# POE_REGULADORES.net
KiCad netlist of a schematic drawn in EAGLE
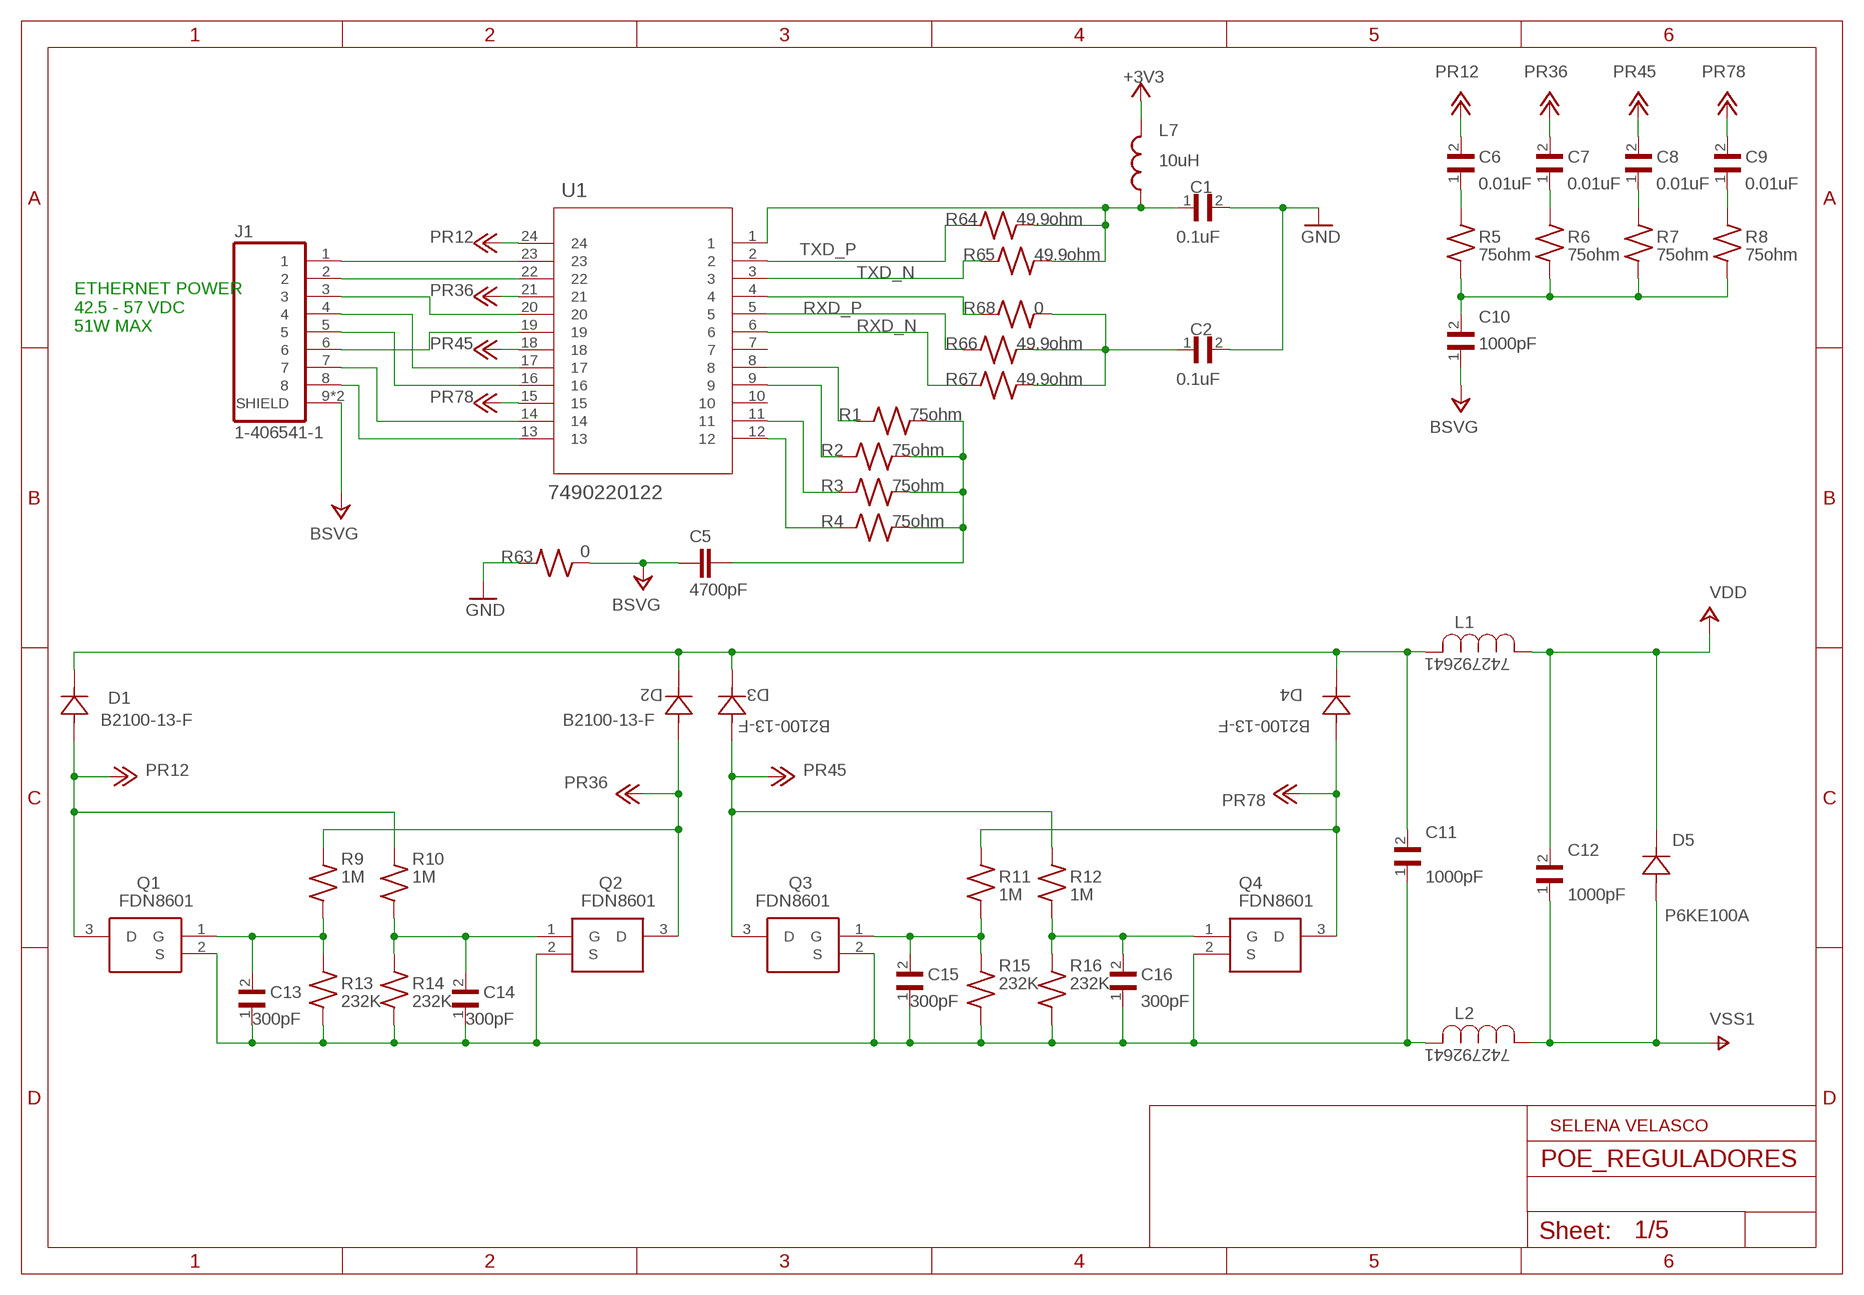
[diagram p0: schematic, sheet 1]
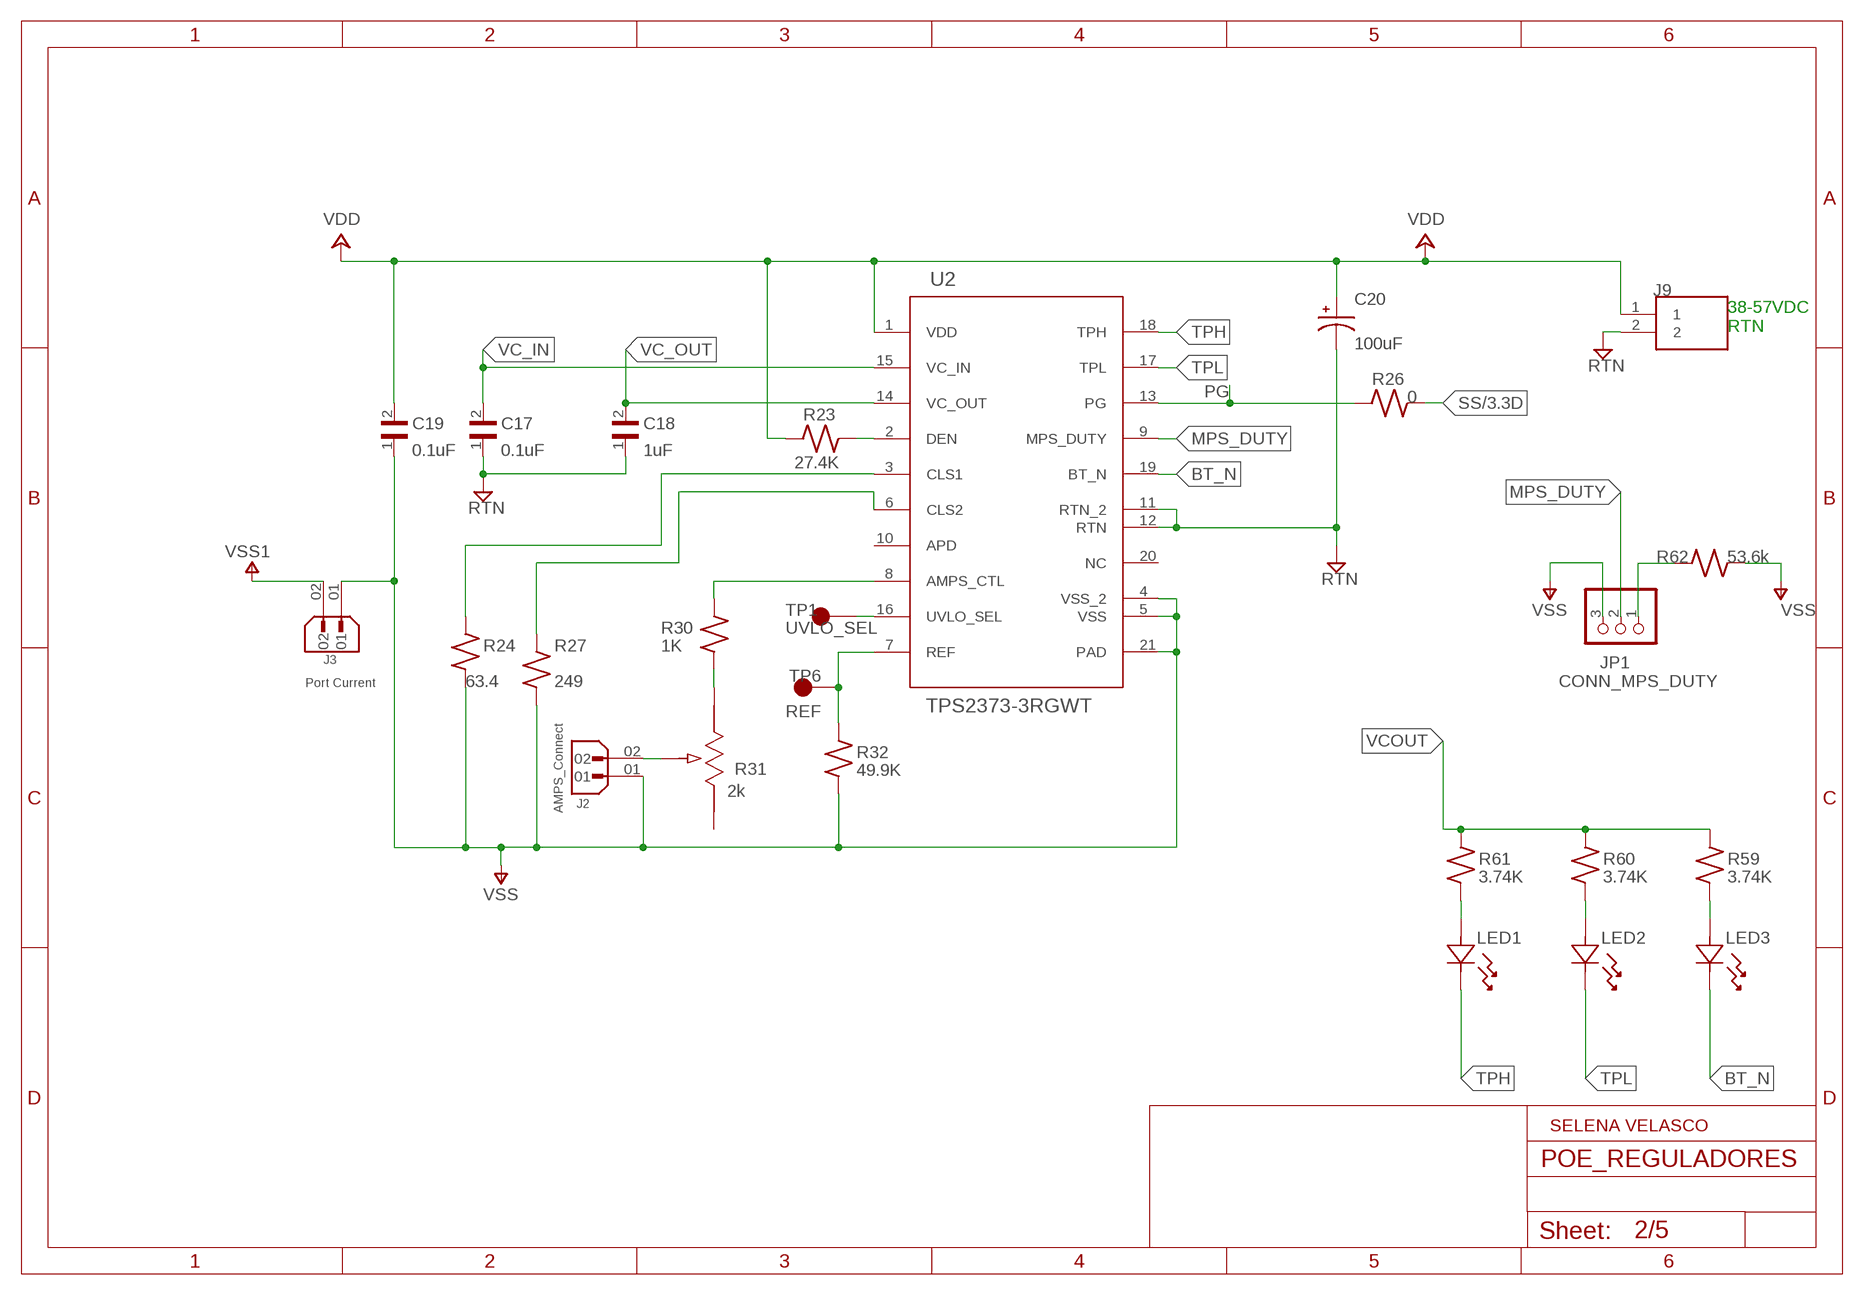
[diagram p1: schematic, sheet 2]
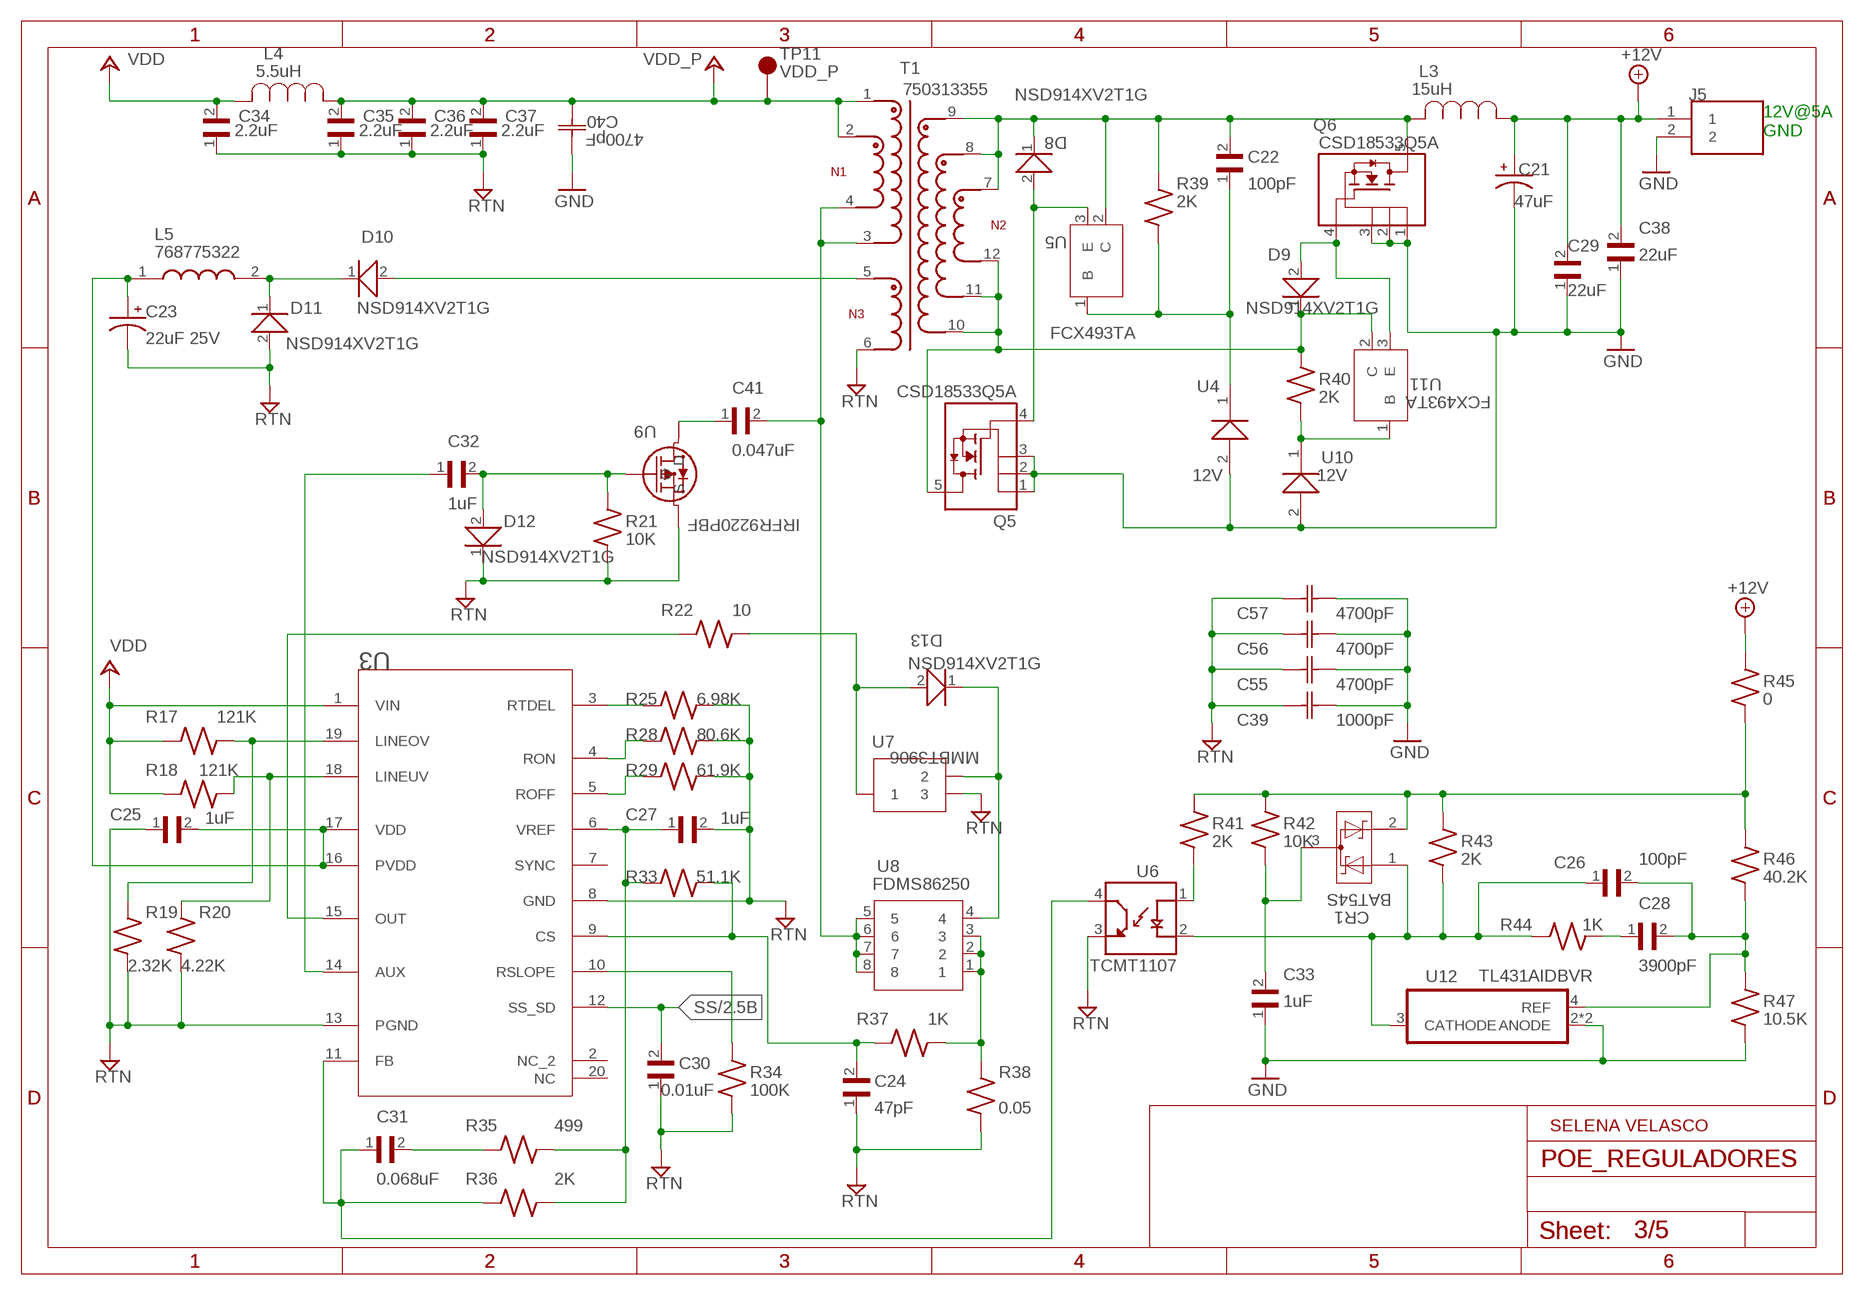
[diagram p2: schematic, sheet 3]
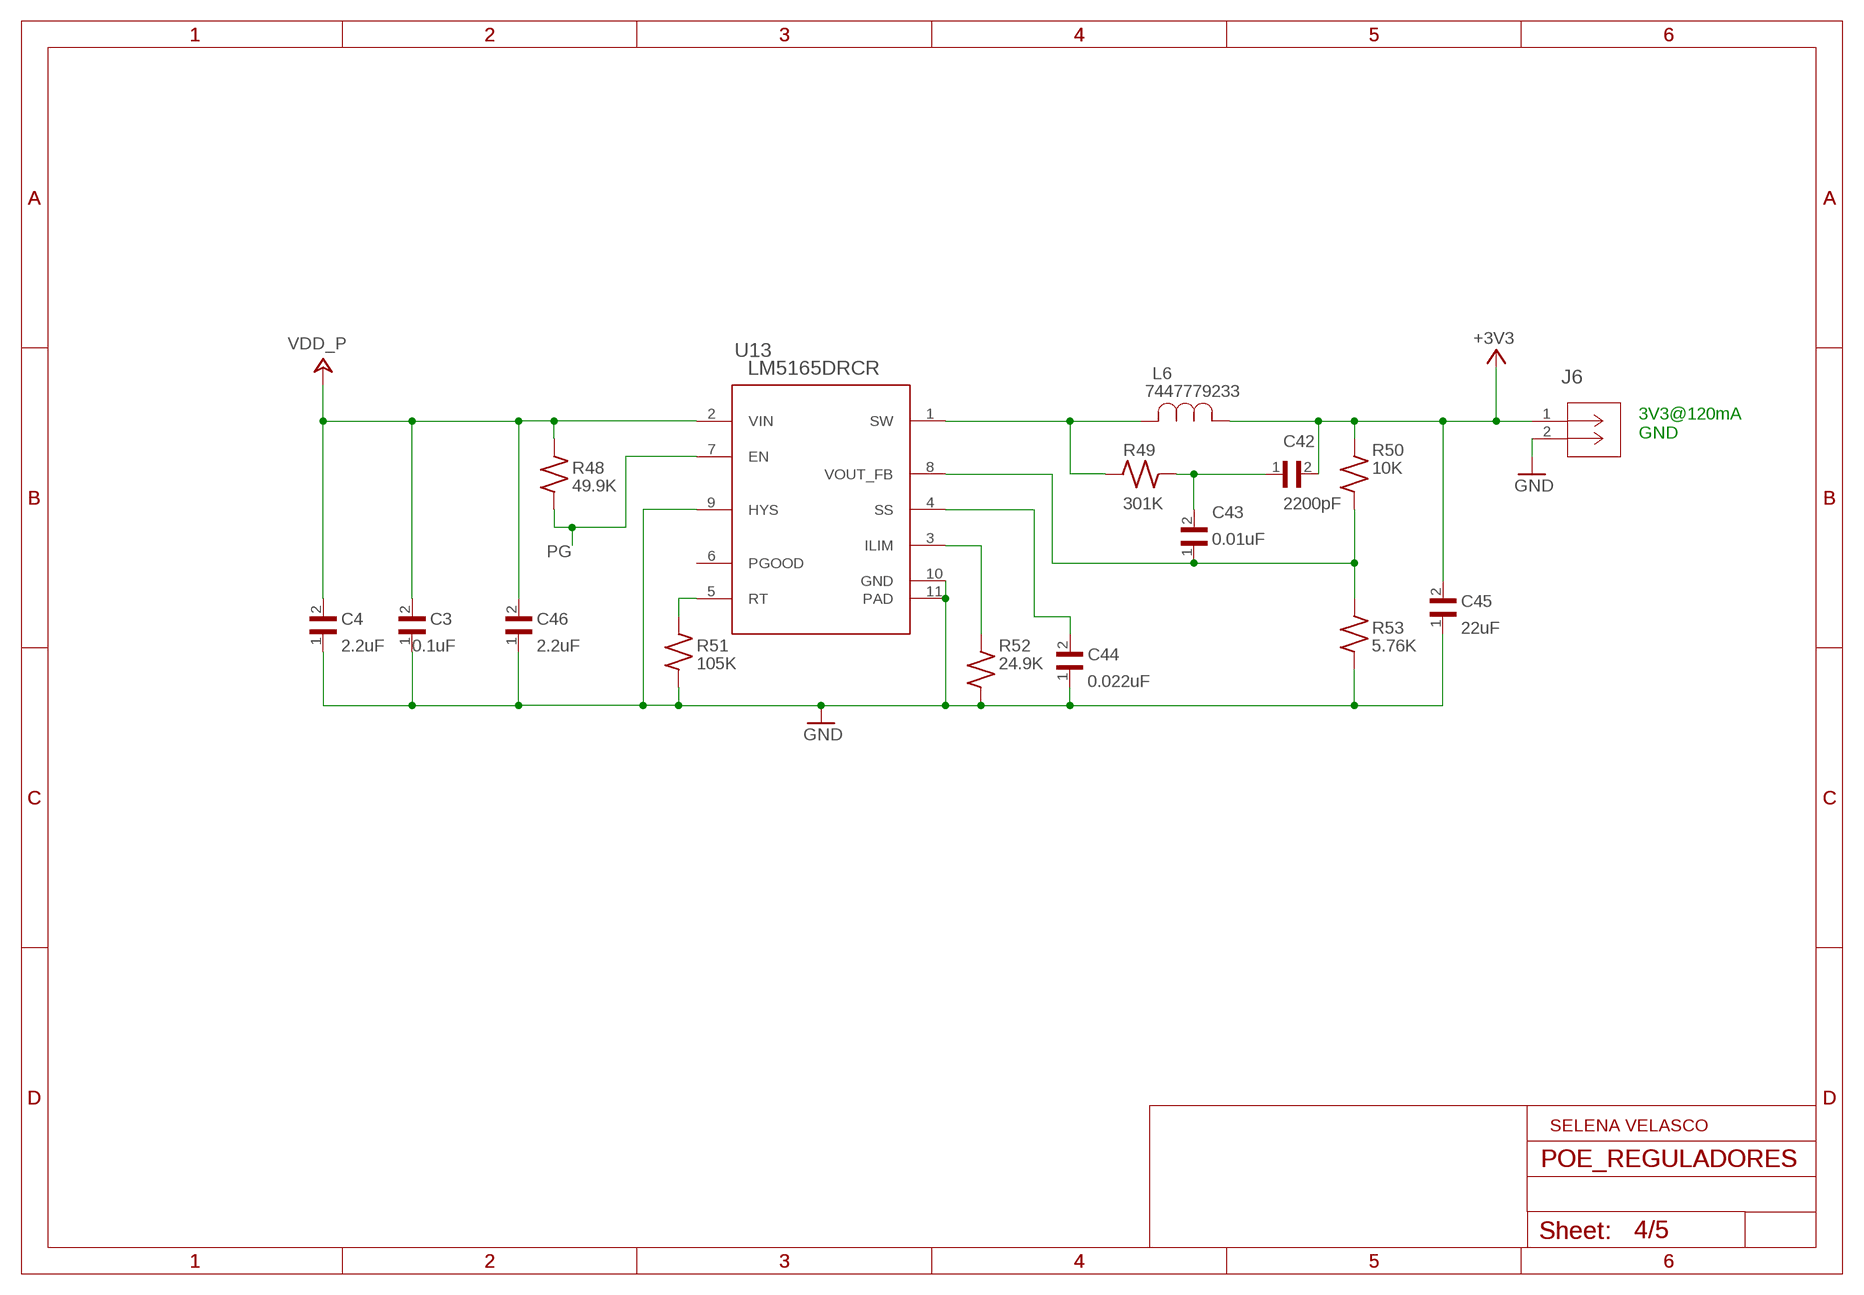
[diagram p3: schematic, sheet 4]
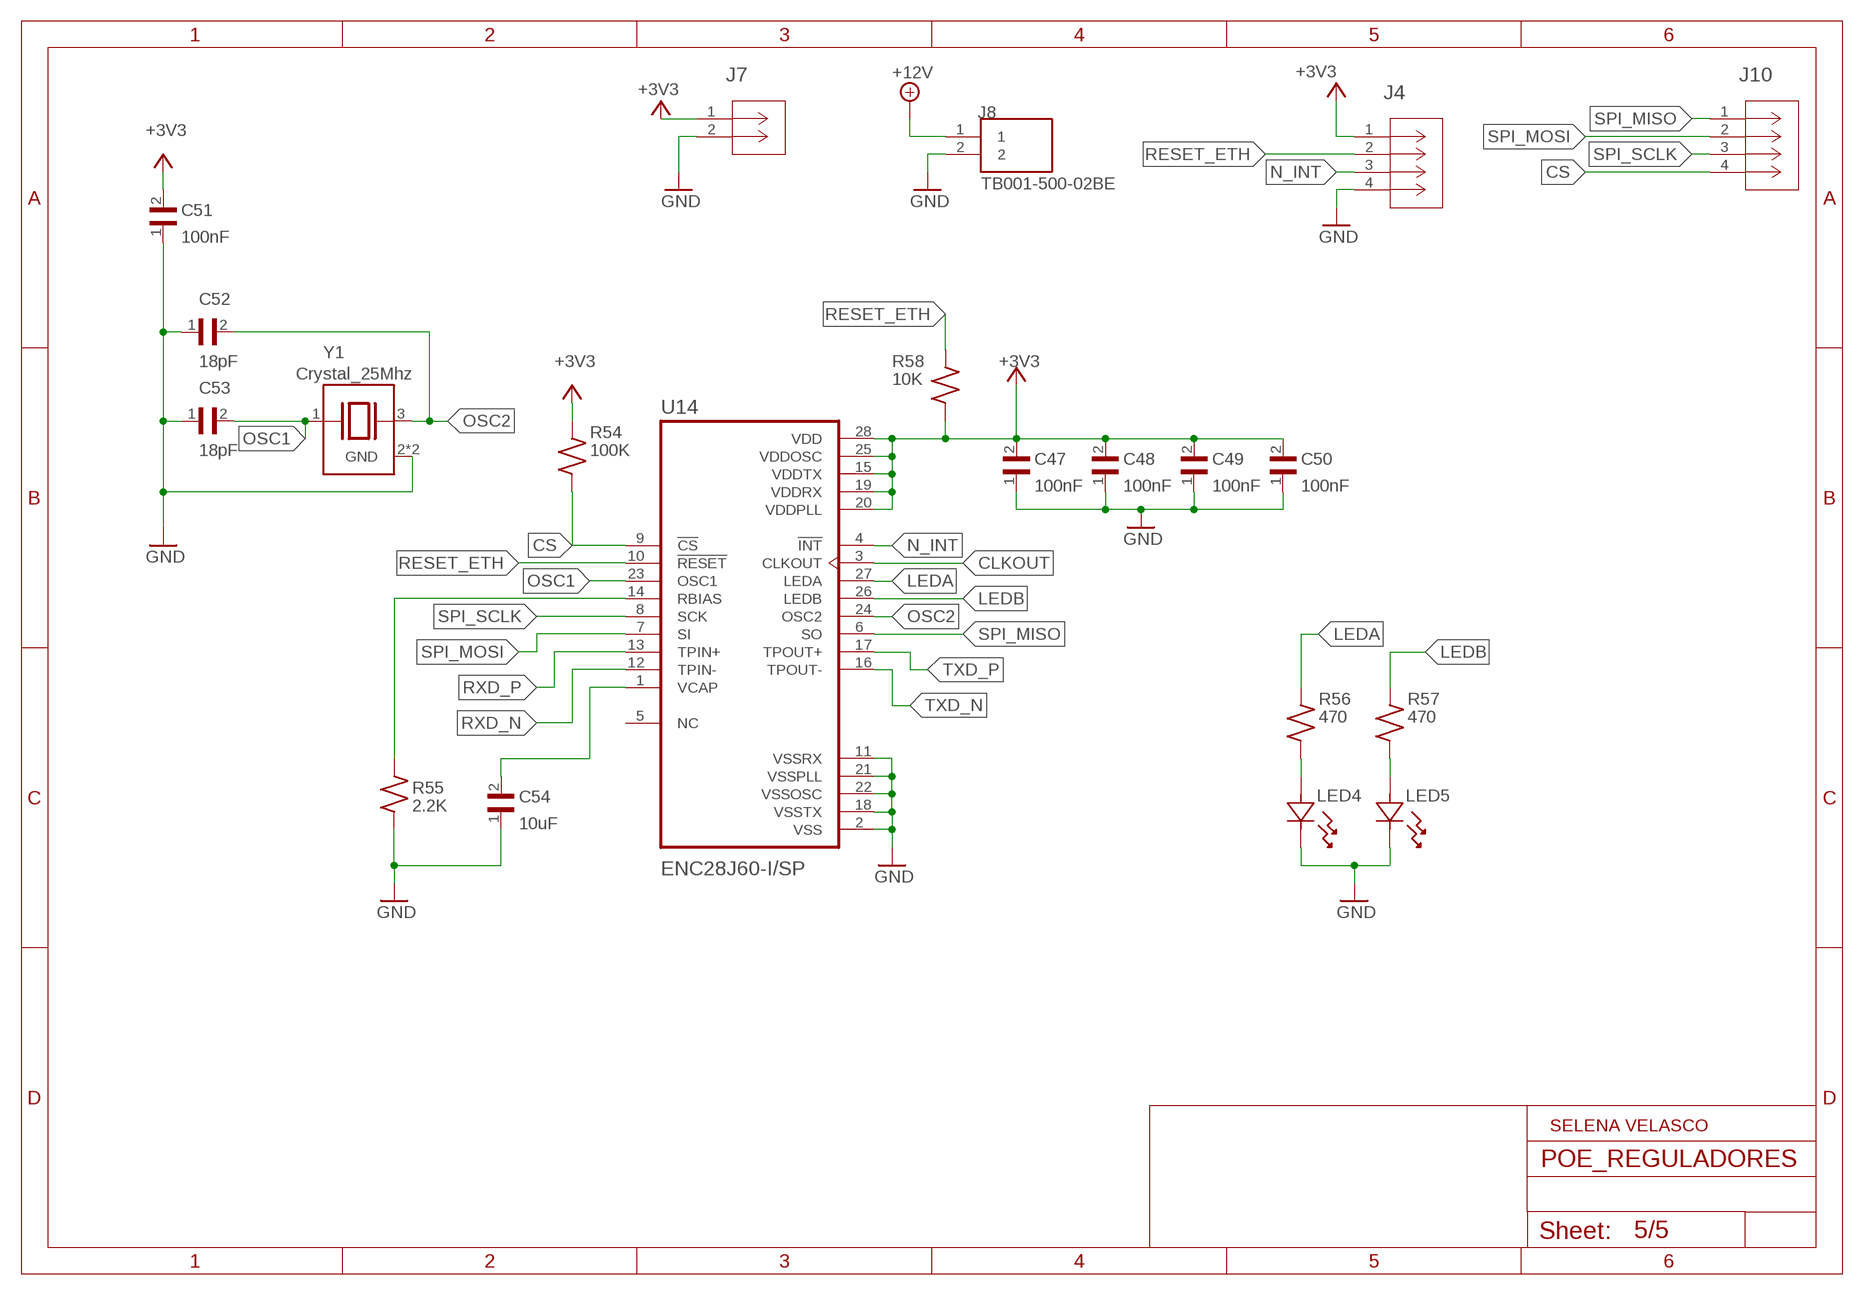
[diagram p4: schematic, sheet 5]

(export (version "E")
  (design (tool "Eeschema 10.0.6"))
  (components
    (comp (ref "C21")
      (value "47uF")
      (footprint "eagle-import:CAP_EEEFK1C470P")
      (fields (field (name "MANUFACTURER") "Panasonic"))
      (libsource (lib "eagle-import") (part "EEEFK1C470P"))
    )
    (comp (ref "C22")
      (value "100pF")
      (footprint "eagle-import:CAPC3316X98N")
      (libsource (lib "eagle-import") (part "C1206Y104K9RAC7800"))
    )
    (comp (ref "C23")
      (value "22uF 25V")
      (footprint "eagle-import:CAP_EEEFK1E220R")
      (fields (field (name "MANUFACTURER") "Panasonic"))
      (libsource (lib "eagle-import") (part "EEEFK1E220R"))
    )
    (comp (ref "C24")
      (value "47pF")
      (footprint "eagle-import:CAPC3316X98N")
      (libsource (lib "eagle-import") (part "C1206Y104K9RAC7800"))
    )
    (comp (ref "C25")
      (value "1uF")
      (footprint "eagle-import:CAPC3316X98N")
      (libsource (lib "eagle-import") (part "C1206Y104K9RAC7800"))
    )
    (comp (ref "C26")
      (value "100pF")
      (footprint "eagle-import:CAPC3316X98N")
      (libsource (lib "eagle-import") (part "C1206Y104K9RAC7800"))
    )
    (comp (ref "C27")
      (value "1uF")
      (footprint "eagle-import:CAPC3316X98N")
      (libsource (lib "eagle-import") (part "C1206Y104K9RAC7800"))
    )
    (comp (ref "C28")
      (value "3900pF")
      (footprint "eagle-import:CAPC3316X98N")
      (libsource (lib "eagle-import") (part "C1206Y104K9RAC7800"))
    )
    (comp (ref "C29")
      (value "22uF")
      (footprint "eagle-import:CAPC3316X98N")
      (libsource (lib "eagle-import") (part "C1206Y104K9RAC7800"))
    )
    (comp (ref "C30")
      (value "0.01uF")
      (footprint "eagle-import:CAPC3316X98N")
      (libsource (lib "eagle-import") (part "C1206Y104K9RAC7800"))
    )
    (comp (ref "C31")
      (value "0.068uF")
      (footprint "eagle-import:CAPC3316X98N")
      (libsource (lib "eagle-import") (part "C1206Y104K9RAC7800"))
    )
    (comp (ref "C32")
      (value "1uF")
      (footprint "eagle-import:CAPC3316X98N")
      (libsource (lib "eagle-import") (part "C1206Y104K9RAC7800"))
    )
    (comp (ref "C33")
      (value "1uF")
      (footprint "eagle-import:CAPC3316X98N")
      (libsource (lib "eagle-import") (part "C1206Y104K9RAC7800"))
    )
    (comp (ref "C34")
      (value "2.2uF")
      (footprint "eagle-import:CAPC3316X98N")
      (libsource (lib "eagle-import") (part "C1206Y104K9RAC7800"))
    )
    (comp (ref "C35")
      (value "2.2uF")
      (footprint "eagle-import:CAPC3316X98N")
      (libsource (lib "eagle-import") (part "C1206Y104K9RAC7800"))
    )
    (comp (ref "C36")
      (value "2.2uF")
      (footprint "eagle-import:CAPC3316X98N")
      (libsource (lib "eagle-import") (part "C1206Y104K9RAC7800"))
    )
    (comp (ref "C37")
      (value "2.2uF")
      (footprint "eagle-import:CAPC3316X98N")
      (libsource (lib "eagle-import") (part "C1206Y104K9RAC7800"))
    )
    (comp (ref "C38")
      (value "22uF")
      (footprint "eagle-import:CAPC3316X98N")
      (libsource (lib "eagle-import") (part "C1206Y104K9RAC7800"))
    )
    (comp (ref "C39")
      (value "1000pF")
      (footprint "eagle-import:CAP_1812_AVX")
      (fields
        (field (name "MANUFACTURER_PART_NUMBER") "1812GC472KAT1A")
        (field (name "COPYRIGHT") "Copyright (C) 2024 Ultra Librarian. All rights reserved.")
      )
      (libsource (lib "eagle-import") (part "1812GC472KAT1A"))
    )
    (comp (ref "C40")
      (value "4700pF")
      (footprint "eagle-import:CAP_1812_AVX")
      (fields
        (field (name "MANUFACTURER_PART_NUMBER") "1812GC472KAT1A")
        (field (name "COPYRIGHT") "Copyright (C) 2024 Ultra Librarian. All rights reserved.")
      )
      (libsource (lib "eagle-import") (part "1812GC472KAT1A"))
    )
    (comp (ref "C41")
      (value "0.047uF")
      (footprint "eagle-import:CAPC3316X98N")
      (libsource (lib "eagle-import") (part "C1206Y104K9RAC7800"))
    )
    (comp (ref "C55")
      (value "4700pF")
      (footprint "eagle-import:CAP_1812_AVX")
      (fields
        (field (name "MANUFACTURER_PART_NUMBER") "1812GC472KAT1A")
        (field (name "COPYRIGHT") "Copyright (C) 2024 Ultra Librarian. All rights reserved.")
      )
      (libsource (lib "eagle-import") (part "1812GC472KAT1A"))
    )
    (comp (ref "C56")
      (value "4700pF")
      (footprint "eagle-import:CAP_1812_AVX")
      (fields
        (field (name "MANUFACTURER_PART_NUMBER") "1812GC472KAT1A")
        (field (name "COPYRIGHT") "Copyright (C) 2024 Ultra Librarian. All rights reserved.")
      )
      (libsource (lib "eagle-import") (part "1812GC472KAT1A"))
    )
    (comp (ref "C57")
      (value "4700pF")
      (footprint "eagle-import:CAP_1812_AVX")
      (fields
        (field (name "MANUFACTURER_PART_NUMBER") "1812GC472KAT1A")
        (field (name "COPYRIGHT") "Copyright (C) 2024 Ultra Librarian. All rights reserved.")
      )
      (libsource (lib "eagle-import") (part "1812GC472KAT1A"))
    )
    (comp (ref "CR1")
      (value "BAT54S")
      (footprint "eagle-import:SOT-23_TO-236_DTC")
      (fields (field (name "COPYRIGHT") "Copyright (C) 2024 Ultra Librarian. All rights reserved."))
      (libsource (lib "eagle-import") (part "BAT54S"))
    )
    (comp (ref "D8")
      (value "NSD914XV2T1G")
      (footprint "eagle-import:SOD-523_0P9X1P3_ONS")
      (fields (field (name "COPYRIGHT") "Copyright (C) 2024 Ultra Librarian. All rights reserved."))
      (libsource (lib "eagle-import") (part "NSD914XV2T1G"))
    )
    (comp (ref "D9")
      (value "NSD914XV2T1G")
      (footprint "eagle-import:SOD-523_0P9X1P3_ONS")
      (fields (field (name "COPYRIGHT") "Copyright (C) 2024 Ultra Librarian. All rights reserved."))
      (libsource (lib "eagle-import") (part "NSD914XV2T1G"))
    )
    (comp (ref "D10")
      (value "NSD914XV2T1G")
      (footprint "eagle-import:SOD-523_0P9X1P3_ONS")
      (fields (field (name "COPYRIGHT") "Copyright (C) 2024 Ultra Librarian. All rights reserved."))
      (libsource (lib "eagle-import") (part "NSD914XV2T1G"))
    )
    (comp (ref "D11")
      (value "NSD914XV2T1G")
      (footprint "eagle-import:SOD-523_0P9X1P3_ONS")
      (fields (field (name "COPYRIGHT") "Copyright (C) 2024 Ultra Librarian. All rights reserved."))
      (libsource (lib "eagle-import") (part "NSD914XV2T1G"))
    )
    (comp (ref "D12")
      (value "NSD914XV2T1G")
      (footprint "eagle-import:SOD-523_0P9X1P3_ONS")
      (fields (field (name "COPYRIGHT") "Copyright (C) 2024 Ultra Librarian. All rights reserved."))
      (libsource (lib "eagle-import") (part "NSD914XV2T1G"))
    )
    (comp (ref "D13")
      (value "NSD914XV2T1G")
      (footprint "eagle-import:SOD-523_0P9X1P3_ONS")
      (fields (field (name "COPYRIGHT") "Copyright (C) 2024 Ultra Librarian. All rights reserved."))
      (libsource (lib "eagle-import") (part "NSD914XV2T1G"))
    )
    (comp (ref "J5")
      (value "TB001-500-02BE")
      (footprint "eagle-import:CUI_TB001-500-02BE")
      (fields (field (name "MANUFACTURER") "CUI"))
      (libsource (lib "eagle-import") (part "TB001-500-02BE"))
    )
    (comp (ref "L3")
      (value "15uH")
      (footprint "eagle-import:IND_1890_2-WE-HCI_WRE")
      (fields
        (field (name "MANUFACTURER_PART_NUMBER") "74435571500")
        (field (name "COPYRIGHT") "Copyright (C) 2024 Ultra Librarian. All rights reserved.")
      )
      (libsource (lib "eagle-import") (part "74435571500"))
    )
    (comp (ref "L4")
      (value "5.5uH")
      (footprint "eagle-import:IND_1050-WE-HCI_WRE")
      (fields
        (field (name "MANUFACTURER_PART_NUMBER") "744325550")
        (field (name "COPYRIGHT") "Copyright (C) 2024 Ultra Librarian. All rights reserved.")
      )
      (libsource (lib "eagle-import") (part "744325550"))
    )
    (comp (ref "L5")
      (value "768775322")
      (footprint "eagle-import:768775322")
      (fields (field (name "MOUSER_PART_NUMBER") "710-768775322"))
      (libsource (lib "eagle-import") (part "768775322"))
    )
    (comp (ref "Q5")
      (value "CSD18533Q5A")
      (footprint "eagle-import:TRANS_CSD18533Q5A")
      (fields (field (name "MANUFACTURER") "Texas Instruments"))
      (libsource (lib "eagle-import") (part "CSD18533Q5A"))
    )
    (comp (ref "Q6")
      (value "CSD18533Q5A")
      (footprint "eagle-import:TRANS_CSD18533Q5A")
      (fields (field (name "MANUFACTURER") "Texas Instruments"))
      (libsource (lib "eagle-import") (part "CSD18533Q5A"))
    )
    (comp (ref "R17")
      (value "121K")
      (footprint "eagle-import:RESC3116X65N")
      (libsource (lib "eagle-import") (part "RC1206FR-071ML"))
    )
    (comp (ref "R18")
      (value "121K")
      (footprint "eagle-import:RESC3116X65N")
      (libsource (lib "eagle-import") (part "RC1206FR-071ML"))
    )
    (comp (ref "R19")
      (value "2.32K")
      (footprint "eagle-import:RESC3116X65N")
      (libsource (lib "eagle-import") (part "RC1206FR-071ML"))
    )
    (comp (ref "R20")
      (value "4.22K")
      (footprint "eagle-import:RESC3116X65N")
      (libsource (lib "eagle-import") (part "RC1206FR-071ML"))
    )
    (comp (ref "R21")
      (value "10K")
      (footprint "eagle-import:RESC3116X65N")
      (libsource (lib "eagle-import") (part "RC1206FR-071ML"))
    )
    (comp (ref "R22")
      (value "10")
      (footprint "eagle-import:RESC3116X65N")
      (libsource (lib "eagle-import") (part "RC1206FR-071ML"))
    )
    (comp (ref "R25")
      (value "6.98K")
      (footprint "eagle-import:RESC3116X65N")
      (libsource (lib "eagle-import") (part "RC1206FR-071ML"))
    )
    (comp (ref "R28")
      (value "80.6K")
      (footprint "eagle-import:RESC3116X65N")
      (libsource (lib "eagle-import") (part "RC1206FR-071ML"))
    )
    (comp (ref "R29")
      (value "61.9K")
      (footprint "eagle-import:RESC3116X65N")
      (libsource (lib "eagle-import") (part "RC1206FR-071ML"))
    )
    (comp (ref "R33")
      (value "51.1K")
      (footprint "eagle-import:RESC3116X65N")
      (libsource (lib "eagle-import") (part "RC1206FR-071ML"))
    )
    (comp (ref "R34")
      (value "100K")
      (footprint "eagle-import:RESC3116X65N")
      (libsource (lib "eagle-import") (part "RC1206FR-071ML"))
    )
    (comp (ref "R35")
      (value "499")
      (footprint "eagle-import:RESC3116X65N")
      (libsource (lib "eagle-import") (part "RC1206FR-071ML"))
    )
    (comp (ref "R36")
      (value "2K")
      (footprint "eagle-import:RESC3116X65N")
      (libsource (lib "eagle-import") (part "RC1206FR-071ML"))
    )
    (comp (ref "R37")
      (value "1K")
      (footprint "eagle-import:RESC3116X65N")
      (libsource (lib "eagle-import") (part "RC1206FR-071ML"))
    )
    (comp (ref "R38")
      (value "0.05")
      (footprint "eagle-import:RESC3116X65N")
      (libsource (lib "eagle-import") (part "RC1206FR-071ML"))
    )
    (comp (ref "R39")
      (value "2K")
      (footprint "eagle-import:RESC3116X65N")
      (libsource (lib "eagle-import") (part "RC1206FR-071ML"))
    )
    (comp (ref "R40")
      (value "2K")
      (footprint "eagle-import:RESC3116X65N")
      (libsource (lib "eagle-import") (part "RC1206FR-071ML"))
    )
    (comp (ref "R41")
      (value "2K")
      (footprint "eagle-import:RESC3116X65N")
      (libsource (lib "eagle-import") (part "RC1206FR-071ML"))
    )
    (comp (ref "R42")
      (value "10K")
      (footprint "eagle-import:RESC3116X65N")
      (libsource (lib "eagle-import") (part "RC1206FR-071ML"))
    )
    (comp (ref "R43")
      (value "2K")
      (footprint "eagle-import:RESC3116X65N")
      (libsource (lib "eagle-import") (part "RC1206FR-071ML"))
    )
    (comp (ref "R44")
      (value "1K")
      (footprint "eagle-import:RESC3116X65N")
      (libsource (lib "eagle-import") (part "RC1206FR-071ML"))
    )
    (comp (ref "R45")
      (value "0")
      (footprint "eagle-import:RESC3116X65N")
      (libsource (lib "eagle-import") (part "RC1206FR-071ML"))
    )
    (comp (ref "R46")
      (value "40.2K")
      (footprint "eagle-import:RESC3116X65N")
      (libsource (lib "eagle-import") (part "RC1206FR-071ML"))
    )
    (comp (ref "R47")
      (value "10.5K")
      (footprint "eagle-import:RESC3116X65N")
      (libsource (lib "eagle-import") (part "RC1206FR-071ML"))
    )
    (comp (ref "T1")
      (value "750313355")
      (footprint "eagle-import:WE-POE++_EFD20_L29.65W21.8H11.43")
      (libsource (lib "eagle-import") (part "750313355"))
    )
    (comp (ref "TP11")
      (value "VDD_P")
      (footprint "eagle-import:KEYSTONE_5019")
      (fields (field (name "MANUFACTURER") "Keystone Electronics"))
      (libsource (lib "eagle-import") (part "5019"))
    )
    (comp (ref "U3")
      (value "UCC2897APW")
      (footprint "eagle-import:PW0020A")
      (fields (field (name "COPYRIGHT") "Copyright (C) 2024 Ultra Librarian. All rights reserved."))
      (libsource (lib "eagle-import") (part "UCC2897APW"))
    )
    (comp (ref "U4")
      (value "12V")
      (footprint "eagle-import:SOD-123_ONS")
      (fields
        (field (name "MANUFACTURER_PART_NUMBER") "MMSZ5242BT3G")
        (field (name "COPYRIGHT") "Copyright (C) 2024 Ultra Librarian. All rights reserved.")
      )
      (libsource (lib "eagle-import") (part "MMSZ5242BT3G"))
    )
    (comp (ref "U5")
      (value "FCX493TA")
      (footprint "eagle-import:FCX493TA_DIO")
      (fields (field (name "COPYRIGHT") "Copyright (C) 2024 Ultra Librarian. All rights reserved."))
      (libsource (lib "eagle-import") (part "FCX493TA"))
    )
    (comp (ref "U6")
      (value "TCMT1107")
      (footprint "eagle-import:SOIC127P700X230-4N")
      (fields (field (name "MANUFACTURER") "Vishay"))
      (libsource (lib "eagle-import") (part "TCMT1107"))
    )
    (comp (ref "U7")
      (value "MMBT3906")
      (footprint "eagle-import:SOT-23-3_1P4X3P040_ONS")
      (fields
        (field (name "MANUFACTURER_PART_NUMBER") "SMMBT3906LT1G")
        (field (name "COPYRIGHT") "Copyright (C) 2024 Ultra Librarian. All rights reserved.")
      )
      (libsource (lib "eagle-import") (part "SMMBT3906LT1G"))
    )
    (comp (ref "U8")
      (value "FDMS86250")
      (footprint "eagle-import:FDMS_86250_ONS")
      (fields (field (name "COPYRIGHT") "Copyright (C) 2024 Ultra Librarian. All rights reserved."))
      (libsource (lib "eagle-import") (part "FDMS86250"))
    )
    (comp (ref "U9")
      (value "IRFR9220PBF")
      (footprint "eagle-import:DPAK_VIS")
      (fields (field (name "COPYRIGHT") "Copyright (C) 2024 Ultra Librarian. All rights reserved."))
      (libsource (lib "eagle-import") (part "IRFR9220PBF"))
    )
    (comp (ref "U10")
      (value "12V")
      (footprint "eagle-import:SOD-123_ONS")
      (fields
        (field (name "MANUFACTURER_PART_NUMBER") "MMSZ5242BT3G")
        (field (name "COPYRIGHT") "Copyright (C) 2024 Ultra Librarian. All rights reserved.")
      )
      (libsource (lib "eagle-import") (part "MMSZ5242BT3G"))
    )
    (comp (ref "U11")
      (value "FCX493TA")
      (footprint "eagle-import:FCX493TA_DIO")
      (fields (field (name "COPYRIGHT") "Copyright (C) 2024 Ultra Librarian. All rights reserved."))
      (libsource (lib "eagle-import") (part "FCX493TA"))
    )
    (comp (ref "U12")
      (value "TL431AIDBVR")
      (footprint "eagle-import:SOT95P280X145-5N")
      (libsource (lib "eagle-import") (part "TL431AIDBVR"))
    )
    (comp (ref "C17")
      (value "0.1uF")
      (footprint "eagle-import:CAPC3316X98N")
      (libsource (lib "eagle-import") (part "C1206Y104K9RAC7800"))
    )
    (comp (ref "C18")
      (value "1uF")
      (footprint "eagle-import:CAPC3316X98N")
      (libsource (lib "eagle-import") (part "C1206Y104K9RAC7800"))
    )
    (comp (ref "C19")
      (value "0.1uF")
      (footprint "eagle-import:CAPC3316X98N")
      (libsource (lib "eagle-import") (part "C1206Y104K9RAC7800"))
    )
    (comp (ref "C20")
      (value "100uF")
      (footprint "eagle-import:CAP_EEEFK1J470P")
      (fields (field (name "MANUFACTURER") "Panasonic"))
      (libsource (lib "eagle-import") (part "EEEFK1J470P"))
    )
    (comp (ref "J2")
      (value "AMPS_Connect")
      (footprint "eagle-import:WURTH_61300211121")
      (fields (field (name "MF") "Würth Elektronik") (field (name "MP") "61300211121"))
      (libsource (lib "eagle-import") (part "61300211121"))
    )
    (comp (ref "J3")
      (value "Port Current")
      (footprint "eagle-import:WURTH_61300211121")
      (fields (field (name "MF") "Würth Elektronik") (field (name "MP") "61300211121"))
      (libsource (lib "eagle-import") (part "61300211121"))
    )
    (comp (ref "J9")
      (value "TB001-500-02BE")
      (footprint "eagle-import:CUI_TB001-500-02BE")
      (fields (field (name "MANUFACTURER") "CUI"))
      (libsource (lib "eagle-import") (part "TB001-500-02BE"))
    )
    (comp (ref "JP1")
      (value "CONN_MPS_DUTY")
      (footprint "eagle-import:1X03")
      (libsource (lib "eagle-import") (part "PINHD-1X3"))
    )
    (comp (ref "LED1")
      (value "BL-BGE1V1")
      (footprint "eagle-import:BL-BGE1V1_AMB")
      (fields (field (name "COPYRIGHT") "Copyright (C) 2024 Ultra Librarian. All rights reserved."))
      (libsource (lib "eagle-import") (part "BL-BGE1V1"))
    )
    (comp (ref "LED2")
      (value "BL-BGE1V1")
      (footprint "eagle-import:BL-BGE1V1_AMB")
      (fields (field (name "COPYRIGHT") "Copyright (C) 2024 Ultra Librarian. All rights reserved."))
      (libsource (lib "eagle-import") (part "BL-BGE1V1"))
    )
    (comp (ref "LED3")
      (value "BL-BGE1V1")
      (footprint "eagle-import:BL-BGE1V1_AMB")
      (fields (field (name "COPYRIGHT") "Copyright (C) 2024 Ultra Librarian. All rights reserved."))
      (libsource (lib "eagle-import") (part "BL-BGE1V1"))
    )
    (comp (ref "R23")
      (value "27.4K")
      (footprint "eagle-import:RESC3116X65N")
      (libsource (lib "eagle-import") (part "RC1206FR-071ML"))
    )
    (comp (ref "R24")
      (value "63.4")
      (footprint "eagle-import:RESC3116X65N")
      (libsource (lib "eagle-import") (part "RC1206FR-071ML"))
    )
    (comp (ref "R26")
      (value "0")
      (footprint "eagle-import:RESC3116X65N")
      (libsource (lib "eagle-import") (part "RC1206FR-071ML"))
    )
    (comp (ref "R27")
      (value "249")
      (footprint "eagle-import:RESC3116X65N")
      (libsource (lib "eagle-import") (part "RC1206FR-071ML"))
    )
    (comp (ref "R30")
      (value "1K")
      (footprint "eagle-import:RESC3116X65N")
      (libsource (lib "eagle-import") (part "RC1206FR-071ML"))
    )
    (comp (ref "R31")
      (value "2k")
      (footprint "eagle-import:POT_3386P")
      (fields
        (field (name "MANUFACTURER_PART_NUMBER") "3386P-1-202LF")
        (field (name "COPYRIGHT") "Copyright (C) 2024 Ultra Librarian. All rights reserved.")
      )
      (libsource (lib "eagle-import") (part "3386P-1-202LF"))
    )
    (comp (ref "R32")
      (value "49.9K")
      (footprint "eagle-import:RESC3116X65N")
      (libsource (lib "eagle-import") (part "RC1206FR-071ML"))
    )
    (comp (ref "R59")
      (value "3.74K")
      (footprint "eagle-import:RESC3116X65N")
      (libsource (lib "eagle-import") (part "RC1206FR-071ML"))
    )
    (comp (ref "R60")
      (value "3.74K")
      (footprint "eagle-import:RESC3116X65N")
      (libsource (lib "eagle-import") (part "RC1206FR-071ML"))
    )
    (comp (ref "R61")
      (value "3.74K")
      (footprint "eagle-import:RESC3116X65N")
      (libsource (lib "eagle-import") (part "RC1206FR-071ML"))
    )
    (comp (ref "R62")
      (value "53.6k")
      (footprint "eagle-import:RESC3116X65N")
      (libsource (lib "eagle-import") (part "RC1206FR-071ML"))
    )
    (comp (ref "TP1")
      (value "UVLO_SEL")
      (footprint "eagle-import:KEYSTONE_5019")
      (fields (field (name "MANUFACTURER") "Keystone Electronics"))
      (libsource (lib "eagle-import") (part "5019"))
    )
    (comp (ref "TP6")
      (value "REF")
      (footprint "eagle-import:KEYSTONE_5019")
      (fields (field (name "MANUFACTURER") "Keystone Electronics"))
      (libsource (lib "eagle-import") (part "5019"))
    )
    (comp (ref "U2")
      (value "TPS2373-3RGWT")
      (footprint "eagle-import:RGW0020B")
      (fields (field (name "COPYRIGHT") "Copyright (C) 2024 Ultra Librarian. All rights reserved."))
      (libsource (lib "eagle-import") (part "TPS2373-3RGWT"))
    )
    (comp (ref "C1")
      (value "0.1uF")
      (footprint "eagle-import:CAPC3316X98N")
      (libsource (lib "eagle-import") (part "C1206Y104K9RAC7800"))
    )
    (comp (ref "C2")
      (value "0.1uF")
      (footprint "eagle-import:CAPC3316X98N")
      (libsource (lib "eagle-import") (part "C1206Y104K9RAC7800"))
    )
    (comp (ref "C5")
      (value "4700pF")
      (footprint "eagle-import:C4532")
      (libsource (lib "eagle-import") (part "C-EUC4532"))
    )
    (comp (ref "C6")
      (value "0.01uF")
      (footprint "eagle-import:CAPC3316X98N")
      (libsource (lib "eagle-import") (part "C1206Y104K9RAC7800"))
    )
    (comp (ref "C7")
      (value "0.01uF")
      (footprint "eagle-import:CAPC3316X98N")
      (libsource (lib "eagle-import") (part "C1206Y104K9RAC7800"))
    )
    (comp (ref "C8")
      (value "0.01uF")
      (footprint "eagle-import:CAPC3316X98N")
      (libsource (lib "eagle-import") (part "C1206Y104K9RAC7800"))
    )
    (comp (ref "C9")
      (value "0.01uF")
      (footprint "eagle-import:CAPC3316X98N")
      (libsource (lib "eagle-import") (part "C1206Y104K9RAC7800"))
    )
    (comp (ref "C10")
      (value "1000pF")
      (footprint "eagle-import:CAPC4520X150N")
      (libsource (lib "eagle-import") (part "GR442QR73D102KW01L"))
    )
    (comp (ref "C11")
      (value "1000pF")
      (footprint "eagle-import:CAPC3316X98N")
      (libsource (lib "eagle-import") (part "C1206Y104K9RAC7800"))
    )
    (comp (ref "C12")
      (value "1000pF")
      (footprint "eagle-import:CAPC3316X98N")
      (libsource (lib "eagle-import") (part "C1206Y104K9RAC7800"))
    )
    (comp (ref "C13")
      (value "300pF")
      (footprint "eagle-import:CAPC3316X98N")
      (libsource (lib "eagle-import") (part "C1206Y104K9RAC7800"))
    )
    (comp (ref "C14")
      (value "300pF")
      (footprint "eagle-import:CAPC3316X98N")
      (libsource (lib "eagle-import") (part "C1206Y104K9RAC7800"))
    )
    (comp (ref "C15")
      (value "300pF")
      (footprint "eagle-import:CAPC3316X98N")
      (libsource (lib "eagle-import") (part "C1206Y104K9RAC7800"))
    )
    (comp (ref "C16")
      (value "300pF")
      (footprint "eagle-import:CAPC3316X98N")
      (libsource (lib "eagle-import") (part "C1206Y104K9RAC7800"))
    )
    (comp (ref "D1")
      (value "B2100-13-F")
      (footprint "eagle-import:SMB_DIO")
      (fields (field (name "COPYRIGHT") "Copyright (C) 2024 Ultra Librarian. All rights reserved."))
      (libsource (lib "eagle-import") (part "B2100-13-F"))
    )
    (comp (ref "D2")
      (value "B2100-13-F")
      (footprint "eagle-import:SMB_DIO")
      (fields (field (name "COPYRIGHT") "Copyright (C) 2024 Ultra Librarian. All rights reserved."))
      (libsource (lib "eagle-import") (part "B2100-13-F"))
    )
    (comp (ref "D3")
      (value "B2100-13-F")
      (footprint "eagle-import:SMB_DIO")
      (fields (field (name "COPYRIGHT") "Copyright (C) 2024 Ultra Librarian. All rights reserved."))
      (libsource (lib "eagle-import") (part "B2100-13-F"))
    )
    (comp (ref "D4")
      (value "B2100-13-F")
      (footprint "eagle-import:SMB_DIO")
      (fields (field (name "COPYRIGHT") "Copyright (C) 2024 Ultra Librarian. All rights reserved."))
      (libsource (lib "eagle-import") (part "B2100-13-F"))
    )
    (comp (ref "D5")
      (value "P6KE100A")
      (footprint "eagle-import:P6KESERIES_LTF")
      (fields (field (name "COPYRIGHT") "Copyright (C) 2024 Ultra Librarian. All rights reserved."))
      (libsource (lib "eagle-import") (part "P6KE100A"))
    )
    (comp (ref "J1")
      (value "1-406541-1")
      (footprint "eagle-import:CONN_1-406541-1")
      (fields (field (name "MANUFACTURER") "TE CONNECTIVITY") (field (name "PUBLISHER") "TE_CONNECTIVITY"))
      (libsource (lib "eagle-import") (part "1-406541-1"))
    )
    (comp (ref "L1")
      (value "742792641")
      (footprint "eagle-import:IND_742792641_WRE")
      (fields (field (name "COPYRIGHT") "Copyright (C) 2024 Ultra Librarian. All rights reserved."))
      (libsource (lib "eagle-import") (part "742792641"))
    )
    (comp (ref "L2")
      (value "742792641")
      (footprint "eagle-import:IND_742792641_WRE")
      (fields (field (name "COPYRIGHT") "Copyright (C) 2024 Ultra Librarian. All rights reserved."))
      (libsource (lib "eagle-import") (part "742792641"))
    )
    (comp (ref "L7")
      (value "10uH")
      (footprint "eagle-import:INDM3225X210N")
      (fields (field (name "MANUFACTURER") "TDK"))
      (libsource (lib "eagle-import") (part "B82422T1103K000"))
    )
    (comp (ref "Q1")
      (value "FDN8601")
      (footprint "eagle-import:SOT95P251X112-3N")
      (fields (field (name "MOUSER_PART_NUMBER") "512-FDN8601"))
      (libsource (lib "eagle-import") (part "FDN8601"))
    )
    (comp (ref "Q2")
      (value "FDN8601")
      (footprint "eagle-import:SOT95P251X112-3N")
      (fields (field (name "MOUSER_PART_NUMBER") "512-FDN8601"))
      (libsource (lib "eagle-import") (part "FDN8601"))
    )
    (comp (ref "Q3")
      (value "FDN8601")
      (footprint "eagle-import:SOT95P251X112-3N")
      (fields (field (name "MOUSER_PART_NUMBER") "512-FDN8601"))
      (libsource (lib "eagle-import") (part "FDN8601"))
    )
    (comp (ref "Q4")
      (value "FDN8601")
      (footprint "eagle-import:SOT95P251X112-3N")
      (fields (field (name "MOUSER_PART_NUMBER") "512-FDN8601"))
      (libsource (lib "eagle-import") (part "FDN8601"))
    )
    (comp (ref "R1")
      (value "75ohm")
      (footprint "eagle-import:RESC3116X65N")
      (libsource (lib "eagle-import") (part "RC1206FR-071ML"))
    )
    (comp (ref "R2")
      (value "75ohm")
      (footprint "eagle-import:RESC3116X65N")
      (libsource (lib "eagle-import") (part "RC1206FR-071ML"))
    )
    (comp (ref "R3")
      (value "75ohm")
      (footprint "eagle-import:RESC3116X65N")
      (libsource (lib "eagle-import") (part "RC1206FR-071ML"))
    )
    (comp (ref "R4")
      (value "75ohm")
      (footprint "eagle-import:RESC3116X65N")
      (libsource (lib "eagle-import") (part "RC1206FR-071ML"))
    )
    (comp (ref "R5")
      (value "75ohm")
      (footprint "eagle-import:RESC3116X65N")
      (libsource (lib "eagle-import") (part "RC1206FR-071ML"))
    )
    (comp (ref "R6")
      (value "75ohm")
      (footprint "eagle-import:RESC3116X65N")
      (libsource (lib "eagle-import") (part "RC1206FR-071ML"))
    )
    (comp (ref "R7")
      (value "75ohm")
      (footprint "eagle-import:RESC3116X65N")
      (libsource (lib "eagle-import") (part "RC1206FR-071ML"))
    )
    (comp (ref "R8")
      (value "75ohm")
      (footprint "eagle-import:RESC3116X65N")
      (libsource (lib "eagle-import") (part "RC1206FR-071ML"))
    )
    (comp (ref "R9")
      (value "1M")
      (footprint "eagle-import:RESC3116X65N")
      (libsource (lib "eagle-import") (part "RC1206FR-071ML"))
    )
    (comp (ref "R10")
      (value "1M")
      (footprint "eagle-import:RESC3116X65N")
      (libsource (lib "eagle-import") (part "RC1206FR-071ML"))
    )
    (comp (ref "R11")
      (value "1M")
      (footprint "eagle-import:RESC3116X65N")
      (libsource (lib "eagle-import") (part "RC1206FR-071ML"))
    )
    (comp (ref "R12")
      (value "1M")
      (footprint "eagle-import:RESC3116X65N")
      (libsource (lib "eagle-import") (part "RC1206FR-071ML"))
    )
    (comp (ref "R13")
      (value "232K")
      (footprint "eagle-import:RESC3116X65N")
      (libsource (lib "eagle-import") (part "RC1206FR-071ML"))
    )
    (comp (ref "R14")
      (value "232K")
      (footprint "eagle-import:RESC3116X65N")
      (libsource (lib "eagle-import") (part "RC1206FR-071ML"))
    )
    (comp (ref "R15")
      (value "232K")
      (footprint "eagle-import:RESC3116X65N")
      (libsource (lib "eagle-import") (part "RC1206FR-071ML"))
    )
    (comp (ref "R16")
      (value "232K")
      (footprint "eagle-import:RESC3116X65N")
      (libsource (lib "eagle-import") (part "RC1206FR-071ML"))
    )
    (comp (ref "R63")
      (value "0")
      (footprint "eagle-import:RESC3116X65N")
      (libsource (lib "eagle-import") (part "RC1206FR-071ML"))
    )
    (comp (ref "R64")
      (value "49.9ohm")
      (footprint "eagle-import:RESC3116X65N")
      (libsource (lib "eagle-import") (part "RC1206FR-071ML"))
    )
    (comp (ref "R65")
      (value "49.9ohm")
      (footprint "eagle-import:RESC3116X65N")
      (libsource (lib "eagle-import") (part "RC1206FR-071ML"))
    )
    (comp (ref "R66")
      (value "49.9ohm")
      (footprint "eagle-import:RESC3116X65N")
      (libsource (lib "eagle-import") (part "RC1206FR-071ML"))
    )
    (comp (ref "R67")
      (value "49.9ohm")
      (footprint "eagle-import:RESC3116X65N")
      (libsource (lib "eagle-import") (part "RC1206FR-071ML"))
    )
    (comp (ref "R68")
      (value "0")
      (footprint "eagle-import:RESC3116X65N")
      (libsource (lib "eagle-import") (part "RC1206FR-071ML"))
    )
    (comp (ref "U1")
      (value "7490220122")
      (footprint "eagle-import:7490220122_WRE")
      (fields (field (name "COPYRIGHT") "Copyright (C) 2024 Ultra Librarian. All rights reserved."))
      (libsource (lib "eagle-import") (part "7490220122"))
    )
    (comp (ref "C47")
      (value "100nF")
      (footprint "eagle-import:CAPC3316X98N")
      (libsource (lib "eagle-import") (part "C1206Y104K9RAC7800"))
    )
    (comp (ref "C48")
      (value "100nF")
      (footprint "eagle-import:CAPC3316X98N")
      (libsource (lib "eagle-import") (part "C1206Y104K9RAC7800"))
    )
    (comp (ref "C49")
      (value "100nF")
      (footprint "eagle-import:CAPC3316X98N")
      (libsource (lib "eagle-import") (part "C1206Y104K9RAC7800"))
    )
    (comp (ref "C50")
      (value "100nF")
      (footprint "eagle-import:CAPC3316X98N")
      (libsource (lib "eagle-import") (part "C1206Y104K9RAC7800"))
    )
    (comp (ref "C51")
      (value "100nF")
      (footprint "eagle-import:CAPC3316X98N")
      (libsource (lib "eagle-import") (part "C1206Y104K9RAC7800"))
    )
    (comp (ref "C52")
      (value "18pF")
      (footprint "eagle-import:CAPC3316X98N")
      (libsource (lib "eagle-import") (part "C1206Y104K9RAC7800"))
    )
    (comp (ref "C53")
      (value "18pF")
      (footprint "eagle-import:CAPC3316X98N")
      (libsource (lib "eagle-import") (part "C1206Y104K9RAC7800"))
    )
    (comp (ref "C54")
      (value "10uF")
      (footprint "eagle-import:CAPC3316X98N")
      (libsource (lib "eagle-import") (part "C1206Y104K9RAC7800"))
    )
    (comp (ref "J4")
      (value "OSTVN04A150")
      (footprint "eagle-import:CONN_OSTVN04A150_OST")
      (fields (field (name "COPYRIGHT") "Copyright (C) 2024 Ultra Librarian. All rights reserved."))
      (libsource (lib "eagle-import") (part "OSTVN04A150"))
    )
    (comp (ref "J7")
      (value "OSTVN02A150")
      (footprint "eagle-import:CONN_OSTVN02A150_OST")
      (fields (field (name "COPYRIGHT") "Copyright (C) 2024 Ultra Librarian. All rights reserved."))
      (libsource (lib "eagle-import") (part "OSTVN02A150"))
    )
    (comp (ref "J8")
      (value "TB001-500-02BE")
      (footprint "eagle-import:CUI_TB001-500-02BE")
      (fields (field (name "MANUFACTURER") "CUI"))
      (libsource (lib "eagle-import") (part "TB001-500-02BE"))
    )
    (comp (ref "J10")
      (value "OSTVN04A150")
      (footprint "eagle-import:CONN_OSTVN04A150_OST")
      (fields (field (name "COPYRIGHT") "Copyright (C) 2024 Ultra Librarian. All rights reserved."))
      (libsource (lib "eagle-import") (part "OSTVN04A150"))
    )
    (comp (ref "LED4")
      (value "BL-BGE1V1")
      (footprint "eagle-import:BL-BGE1V1_AMB")
      (fields (field (name "COPYRIGHT") "Copyright (C) 2024 Ultra Librarian. All rights reserved."))
      (libsource (lib "eagle-import") (part "BL-BGE1V1"))
    )
    (comp (ref "LED5")
      (value "BL-BGE1V1")
      (footprint "eagle-import:BL-BGE1V1_AMB")
      (fields (field (name "COPYRIGHT") "Copyright (C) 2024 Ultra Librarian. All rights reserved."))
      (libsource (lib "eagle-import") (part "BL-BGE1V1"))
    )
    (comp (ref "R54")
      (value "100K")
      (footprint "eagle-import:RESC3116X65N")
      (libsource (lib "eagle-import") (part "RC1206FR-071ML"))
    )
    (comp (ref "R55")
      (value "2.2K")
      (footprint "eagle-import:RESC3116X65N")
      (libsource (lib "eagle-import") (part "RC1206FR-071ML"))
    )
    (comp (ref "R56")
      (value "470")
      (footprint "eagle-import:RESC3116X65N")
      (libsource (lib "eagle-import") (part "RC1206FR-071ML"))
    )
    (comp (ref "R57")
      (value "470")
      (footprint "eagle-import:RESC3116X65N")
      (libsource (lib "eagle-import") (part "RC1206FR-071ML"))
    )
    (comp (ref "R58")
      (value "10K")
      (footprint "eagle-import:RESC3116X65N")
      (libsource (lib "eagle-import") (part "RC1206FR-071ML"))
    )
    (comp (ref "U14")
      (value "ENC28J60-I/SP")
      (footprint "eagle-import:DIP787W45P254L3556H508Q28")
      (libsource (lib "eagle-import") (part "ENC28J60-I/SP"))
    )
    (comp (ref "Y1")
      (value "Crystal_25Mhz")
      (footprint "eagle-import:XTAL_TSX-3225_25.0000MF10P-C3")
      (fields (field (name "MANUFACTURER") "EPSON"))
      (libsource (lib "eagle-import") (part "TSX-3225_25.0000MF10P-C3"))
    )
    (comp (ref "C3")
      (value "0.1uF")
      (footprint "eagle-import:CAPC3316X98N")
      (libsource (lib "eagle-import") (part "C1206Y104K9RAC7800"))
    )
    (comp (ref "C4")
      (value "2.2uF")
      (footprint "eagle-import:CAPC3316X98N")
      (libsource (lib "eagle-import") (part "C1206Y104K9RAC7800"))
    )
    (comp (ref "C42")
      (value "2200pF")
      (footprint "eagle-import:CAPC3316X98N")
      (libsource (lib "eagle-import") (part "C1206Y104K9RAC7800"))
    )
    (comp (ref "C43")
      (value "0.01uF")
      (footprint "eagle-import:CAPC3316X98N")
      (libsource (lib "eagle-import") (part "C1206Y104K9RAC7800"))
    )
    (comp (ref "C44")
      (value "0.022uF")
      (footprint "eagle-import:CAPC3316X98N")
      (libsource (lib "eagle-import") (part "C1206Y104K9RAC7800"))
    )
    (comp (ref "C45")
      (value "22uF")
      (footprint "eagle-import:CAPC3316X98N")
      (libsource (lib "eagle-import") (part "C1206Y104K9RAC7800"))
    )
    (comp (ref "C46")
      (value "2.2uF")
      (footprint "eagle-import:CAPC3316X98N")
      (libsource (lib "eagle-import") (part "C1206Y104K9RAC7800"))
    )
    (comp (ref "J6")
      (value "OSTVN02A150")
      (footprint "eagle-import:CONN_OSTVN02A150_OST")
      (fields (field (name "COPYRIGHT") "Copyright (C) 2024 Ultra Librarian. All rights reserved."))
      (libsource (lib "eagle-import") (part "OSTVN02A150"))
    )
    (comp (ref "L6")
      (value "7447779233")
      (footprint "eagle-import:IND_7345R_WE-PD_WRE")
      (fields (field (name "COPYRIGHT") "Copyright (C) 2024 Ultra Librarian. All rights reserved."))
      (libsource (lib "eagle-import") (part "7447779233"))
    )
    (comp (ref "R48")
      (value "49.9K")
      (footprint "eagle-import:RESC3116X65N")
      (libsource (lib "eagle-import") (part "RC1206FR-071ML"))
    )
    (comp (ref "R49")
      (value "301K")
      (footprint "eagle-import:RESC3116X65N")
      (libsource (lib "eagle-import") (part "RC1206FR-071ML"))
    )
    (comp (ref "R50")
      (value "10K")
      (footprint "eagle-import:RESC3116X65N")
      (libsource (lib "eagle-import") (part "RC1206FR-071ML"))
    )
    (comp (ref "R51")
      (value "105K")
      (footprint "eagle-import:RESC3116X65N")
      (libsource (lib "eagle-import") (part "RC1206FR-071ML"))
    )
    (comp (ref "R52")
      (value "24.9K")
      (footprint "eagle-import:RESC3116X65N")
      (libsource (lib "eagle-import") (part "RC1206FR-071ML"))
    )
    (comp (ref "R53")
      (value "5.76K")
      (footprint "eagle-import:RESC3116X65N")
      (libsource (lib "eagle-import") (part "RC1206FR-071ML"))
    )
    (comp (ref "U13")
      (value "LM5165DRCR")
      (footprint "eagle-import:DRC0010J")
      (fields (field (name "COPYRIGHT") "Copyright (C) 2024 Ultra Librarian. All rights reserved."))
      (libsource (lib "eagle-import") (part "LM5165DRCR"))
    )
  )
  (nets
    (net (code "1") (name "+3V3") (class "Default")
      (node (ref "C42") (pin "2") (pinfunction "2_2") (pintype "passive"))
      (node (ref "C45") (pin "2") (pinfunction "2_2") (pintype "passive"))
      (node (ref "C47") (pin "2") (pinfunction "2_2") (pintype "passive"))
      (node (ref "C48") (pin "2") (pinfunction "2_2") (pintype "passive"))
      (node (ref "C49") (pin "2") (pinfunction "2_2") (pintype "passive"))
      (node (ref "C50") (pin "2") (pinfunction "2_2") (pintype "passive"))
      (node (ref "C51") (pin "2") (pinfunction "2_2") (pintype "passive"))
      (node (ref "J4") (pin "1") (pinfunction "1_1") (pintype "passive"))
      (node (ref "J6") (pin "1") (pinfunction "1_1") (pintype "passive"))
      (node (ref "J7") (pin "1") (pinfunction "1_1") (pintype "passive"))
      (node (ref "L6") (pin "1") (pinfunction "1_1") (pintype "passive"))
      (node (ref "L7") (pin "2") (pinfunction "2_2") (pintype "passive"))
      (node (ref "R50") (pin "2") (pinfunction "2_2") (pintype "passive"))
      (node (ref "R54") (pin "2") (pinfunction "2_2") (pintype "passive"))
      (node (ref "R58") (pin "1") (pinfunction "1_1") (pintype "passive"))
      (node (ref "U14") (pin "15") (pinfunction "VDDTX_15") (pintype "power_in"))
      (node (ref "U14") (pin "19") (pinfunction "VDDRX_19") (pintype "power_in"))
      (node (ref "U14") (pin "20") (pinfunction "VDDPLL_20") (pintype "power_in"))
      (node (ref "U14") (pin "25") (pinfunction "VDDOSC_25") (pintype "power_in"))
      (node (ref "U14") (pin "28") (pinfunction "VDD_28") (pintype "power_in"))
    )
    (net (code "2") (name "+12V") (class "Default")
      (node (ref "C21") (pin "1") (pinfunction "1_1") (pintype "passive"))
      (node (ref "C29") (pin "2") (pinfunction "2_2") (pintype "passive"))
      (node (ref "C38") (pin "2") (pinfunction "2_2") (pintype "passive"))
      (node (ref "J5") (pin "1") (pinfunction "1_1") (pintype "passive"))
      (node (ref "J8") (pin "1") (pinfunction "1_1") (pintype "passive"))
      (node (ref "L3") (pin "1") (pinfunction "1_1") (pintype "passive"))
      (node (ref "R45") (pin "2") (pinfunction "2_2") (pintype "passive"))
    )
    (net (code "3") (name "BSVG") (class "Default")
      (node (ref "C10") (pin "1") (pinfunction "1_1") (pintype "passive"))
      (node (ref "C5") (pin "1") (pinfunction "1_1") (pintype "passive"))
      (node (ref "J1") (pin "10") (pinfunction "SHIELD_10") (pintype "passive"))
      (node (ref "J1") (pin "9") (pinfunction "SHIELD_9") (pintype "passive"))
      (node (ref "R63") (pin "1") (pinfunction "1_1") (pintype "passive"))
    )
    (net (code "4") (name "BT_N") (class "Default")
      (node (ref "LED3") (pin "1") (pinfunction "1_1") (pintype "passive"))
      (node (ref "U2") (pin "19") (pinfunction "BT_N_19") (pintype "input"))
    )
    (net (code "5") (name "CLKOUT") (class "Default")
      (node (ref "U14") (pin "3") (pinfunction "CLKOUT_3") (pintype "output"))
    )
    (net (code "6") (name "CS") (class "Default")
      (node (ref "J10") (pin "4") (pinfunction "4_4") (pintype "passive"))
      (node (ref "R54") (pin "1") (pinfunction "1_1") (pintype "passive"))
      (node (ref "U14") (pin "9") (pinfunction "~{CS}_9") (pintype "input"))
    )
    (net (code "7") (name "GND") (class "Default")
      (node (ref "C1") (pin "2") (pinfunction "2_2") (pintype "passive"))
      (node (ref "C2") (pin "2") (pinfunction "2_2") (pintype "passive"))
      (node (ref "C21") (pin "2") (pinfunction "2_2") (pintype "passive"))
      (node (ref "C29") (pin "1") (pinfunction "1_1") (pintype "passive"))
      (node (ref "C3") (pin "1") (pinfunction "1_1") (pintype "passive"))
      (node (ref "C33") (pin "1") (pinfunction "1_1") (pintype "passive"))
      (node (ref "C38") (pin "1") (pinfunction "1_1") (pintype "passive"))
      (node (ref "C39") (pin "2") (pinfunction "2_2") (pintype "passive"))
      (node (ref "C4") (pin "1") (pinfunction "1_1") (pintype "passive"))
      (node (ref "C40") (pin "1") (pinfunction "1_1") (pintype "passive"))
      (node (ref "C44") (pin "1") (pinfunction "1_1") (pintype "passive"))
      (node (ref "C45") (pin "1") (pinfunction "1_1") (pintype "passive"))
      (node (ref "C46") (pin "1") (pinfunction "1_1") (pintype "passive"))
      (node (ref "C47") (pin "1") (pinfunction "1_1") (pintype "passive"))
      (node (ref "C48") (pin "1") (pinfunction "1_1") (pintype "passive"))
      (node (ref "C49") (pin "1") (pinfunction "1_1") (pintype "passive"))
      (node (ref "C50") (pin "1") (pinfunction "1_1") (pintype "passive"))
      (node (ref "C51") (pin "1") (pinfunction "1_1") (pintype "passive"))
      (node (ref "C52") (pin "1") (pinfunction "1_1") (pintype "passive"))
      (node (ref "C53") (pin "1") (pinfunction "1_1") (pintype "passive"))
      (node (ref "C54") (pin "1") (pinfunction "1_1") (pintype "passive"))
      (node (ref "C55") (pin "2") (pinfunction "2_2") (pintype "passive"))
      (node (ref "C56") (pin "2") (pinfunction "2_2") (pintype "passive"))
      (node (ref "C57") (pin "2") (pinfunction "2_2") (pintype "passive"))
      (node (ref "J4") (pin "4") (pinfunction "4_4") (pintype "passive"))
      (node (ref "J5") (pin "2") (pinfunction "2_2") (pintype "passive"))
      (node (ref "J6") (pin "2") (pinfunction "2_2") (pintype "passive"))
      (node (ref "J7") (pin "2") (pinfunction "2_2") (pintype "passive"))
      (node (ref "J8") (pin "2") (pinfunction "2_2") (pintype "passive"))
      (node (ref "LED4") (pin "1") (pinfunction "1_1") (pintype "passive"))
      (node (ref "LED5") (pin "1") (pinfunction "1_1") (pintype "passive"))
      (node (ref "Q5") (pin "1") (pinfunction "S_1_1") (pintype "passive"))
      (node (ref "Q5") (pin "2") (pinfunction "S_2_2") (pintype "passive"))
      (node (ref "Q5") (pin "3") (pinfunction "S_3_3") (pintype "passive"))
      (node (ref "Q6") (pin "1") (pinfunction "S_1_1") (pintype "passive"))
      (node (ref "Q6") (pin "2") (pinfunction "S_2_2") (pintype "passive"))
      (node (ref "Q6") (pin "3") (pinfunction "S_3_3") (pintype "passive"))
      (node (ref "R47") (pin "1") (pinfunction "1_1") (pintype "passive"))
      (node (ref "R51") (pin "1") (pinfunction "1_1") (pintype "passive"))
      (node (ref "R52") (pin "1") (pinfunction "1_1") (pintype "passive"))
      (node (ref "R53") (pin "1") (pinfunction "1_1") (pintype "passive"))
      (node (ref "R55") (pin "1") (pinfunction "1_1") (pintype "passive"))
      (node (ref "R63") (pin "2") (pinfunction "2_2") (pintype "passive"))
      (node (ref "U10") (pin "2") (pinfunction "ANODE_2") (pintype "passive"))
      (node (ref "U12") (pin "2") (pinfunction "ANODE_2") (pintype "input"))
      (node (ref "U12") (pin "5") (pinfunction "ANODE_5") (pintype "input"))
      (node (ref "U13") (pin "10") (pinfunction "GND_10") (pintype "power_in"))
      (node (ref "U13") (pin "11") (pinfunction "PAD_11") (pintype "power_in"))
      (node (ref "U13") (pin "9") (pinfunction "HYS_9") (pintype "passive"))
      (node (ref "U14") (pin "11") (pinfunction "VSSRX_11") (pintype "power_in"))
      (node (ref "U14") (pin "18") (pinfunction "VSSTX_18") (pintype "power_in"))
      (node (ref "U14") (pin "2") (pinfunction "VSS_2") (pintype "power_in"))
      (node (ref "U14") (pin "21") (pinfunction "VSSPLL_21") (pintype "power_in"))
      (node (ref "U14") (pin "22") (pinfunction "VSSOSC_22") (pintype "power_in"))
      (node (ref "U4") (pin "2") (pinfunction "ANODE_2") (pintype "passive"))
      (node (ref "Y1") (pin "2") (pinfunction "GND_2") (pintype "power_in"))
      (node (ref "Y1") (pin "4") (pinfunction "GND_4") (pintype "power_in"))
    )
    (net (code "8") (name "LEDA") (class "Default")
      (node (ref "R56") (pin "2") (pinfunction "2_2") (pintype "passive"))
      (node (ref "U14") (pin "27") (pinfunction "LEDA_27") (pintype "output"))
    )
    (net (code "9") (name "LEDB") (class "Default")
      (node (ref "R57") (pin "2") (pinfunction "2_2") (pintype "passive"))
      (node (ref "U14") (pin "26") (pinfunction "LEDB_26") (pintype "output"))
    )
    (net (code "10") (name "MPS_DUTY") (class "Default")
      (node (ref "JP1") (pin "2") (pinfunction "2_2") (pintype "passive"))
      (node (ref "U2") (pin "9") (pinfunction "MPS_DUTY_9") (pintype "output"))
    )
    (net (code "11") (name "N_INT") (class "Default")
      (node (ref "J4") (pin "3") (pinfunction "3_3") (pintype "passive"))
      (node (ref "U14") (pin "4") (pinfunction "~{INT}_4") (pintype "output"))
    )
    (net (code "12") (name "Net-(C1-Pad1)") (class "Default")
      (node (ref "C1") (pin "1") (pinfunction "1_1") (pintype "passive"))
      (node (ref "L7") (pin "1") (pinfunction "1_1") (pintype "passive"))
      (node (ref "R64") (pin "2") (pinfunction "2_2") (pintype "passive"))
      (node (ref "R65") (pin "2") (pinfunction "2_2") (pintype "passive"))
      (node (ref "U1") (pin "1") (pinfunction "1_1") (pintype "passive"))
    )
    (net (code "13") (name "Net-(C2-Pad1)") (class "Default")
      (node (ref "C2") (pin "1") (pinfunction "1_1") (pintype "passive"))
      (node (ref "R66") (pin "2") (pinfunction "2_2") (pintype "passive"))
      (node (ref "R67") (pin "2") (pinfunction "2_2") (pintype "passive"))
      (node (ref "R68") (pin "2") (pinfunction "2_2") (pintype "passive"))
    )
    (net (code "14") (name "Net-(C5-Pad2)") (class "Default")
      (node (ref "C5") (pin "2") (pinfunction "2_2") (pintype "passive"))
      (node (ref "R1") (pin "2") (pinfunction "2_2") (pintype "passive"))
      (node (ref "R2") (pin "2") (pinfunction "2_2") (pintype "passive"))
      (node (ref "R3") (pin "2") (pinfunction "2_2") (pintype "passive"))
      (node (ref "R4") (pin "2") (pinfunction "2_2") (pintype "passive"))
    )
    (net (code "15") (name "Net-(C6-Pad1)") (class "Default")
      (node (ref "C6") (pin "1") (pinfunction "1_1") (pintype "passive"))
      (node (ref "R5") (pin "2") (pinfunction "2_2") (pintype "passive"))
    )
    (net (code "16") (name "Net-(C7-Pad1)") (class "Default")
      (node (ref "C7") (pin "1") (pinfunction "1_1") (pintype "passive"))
      (node (ref "R6") (pin "2") (pinfunction "2_2") (pintype "passive"))
    )
    (net (code "17") (name "Net-(C8-Pad1)") (class "Default")
      (node (ref "C8") (pin "1") (pinfunction "1_1") (pintype "passive"))
      (node (ref "R7") (pin "2") (pinfunction "2_2") (pintype "passive"))
    )
    (net (code "18") (name "Net-(C9-Pad1)") (class "Default")
      (node (ref "C9") (pin "1") (pinfunction "1_1") (pintype "passive"))
      (node (ref "R8") (pin "2") (pinfunction "2_2") (pintype "passive"))
    )
    (net (code "19") (name "Net-(C10-Pad2)") (class "Default")
      (node (ref "C10") (pin "2") (pinfunction "2_2") (pintype "passive"))
      (node (ref "R5") (pin "1") (pinfunction "1_1") (pintype "passive"))
      (node (ref "R6") (pin "1") (pinfunction "1_1") (pintype "passive"))
      (node (ref "R7") (pin "1") (pinfunction "1_1") (pintype "passive"))
      (node (ref "R8") (pin "1") (pinfunction "1_1") (pintype "passive"))
    )
    (net (code "20") (name "Net-(C11-Pad2)") (class "Default")
      (node (ref "C11") (pin "2") (pinfunction "2_2") (pintype "passive"))
      (node (ref "D1") (pin "1") (pinfunction "1_1") (pintype "passive"))
      (node (ref "D2") (pin "1") (pinfunction "1_1") (pintype "passive"))
      (node (ref "D3") (pin "1") (pinfunction "1_1") (pintype "passive"))
      (node (ref "D4") (pin "1") (pinfunction "1_1") (pintype "passive"))
      (node (ref "L1") (pin "2") (pinfunction "2_2") (pintype "passive"))
    )
    (net (code "21") (name "Net-(C28-Pad1)") (class "Default")
      (node (ref "C28") (pin "1") (pinfunction "1_1") (pintype "passive"))
      (node (ref "R44") (pin "1") (pinfunction "1_1") (pintype "passive"))
    )
    (net (code "22") (name "Net-(C31-Pad2)") (class "Default")
      (node (ref "C31") (pin "2") (pinfunction "2_2") (pintype "passive"))
      (node (ref "R35") (pin "1") (pinfunction "1_1") (pintype "passive"))
    )
    (net (code "23") (name "Net-(C42-Pad1)") (class "Default")
      (node (ref "C42") (pin "1") (pinfunction "1_1") (pintype "passive"))
      (node (ref "C43") (pin "2") (pinfunction "2_2") (pintype "passive"))
      (node (ref "R49") (pin "2") (pinfunction "2_2") (pintype "passive"))
    )
    (net (code "24") (name "Net-(CR1-ANODE1)") (class "Default")
      (node (ref "C26") (pin "1") (pinfunction "1_1") (pintype "passive"))
      (node (ref "CR1") (pin "1") (pinfunction "ANODE1_1") (pintype "passive"))
      (node (ref "R43") (pin "1") (pinfunction "1_1") (pintype "passive"))
      (node (ref "R44") (pin "2") (pinfunction "2_2") (pintype "passive"))
      (node (ref "U12") (pin "3") (pinfunction "CATHODE_3") (pintype "output"))
      (node (ref "U6") (pin "2") (pinfunction "C_2") (pintype "passive"))
    )
    (net (code "25") (name "Net-(CR1-CATHODE1{slash}ANODE2)") (class "Default")
      (node (ref "C33") (pin "2") (pinfunction "2_2") (pintype "passive"))
      (node (ref "CR1") (pin "3") (pinfunction "CATHODE1/ANODE2_3") (pintype "passive"))
      (node (ref "R42") (pin "1") (pinfunction "1_1") (pintype "passive"))
    )
    (net (code "26") (name "Net-(CR1-CATHODE2)") (class "Default")
      (node (ref "CR1") (pin "2") (pinfunction "CATHODE2_2") (pintype "passive"))
      (node (ref "R41") (pin "2") (pinfunction "2_2") (pintype "passive"))
      (node (ref "R42") (pin "2") (pinfunction "2_2") (pintype "passive"))
      (node (ref "R43") (pin "2") (pinfunction "2_2") (pintype "passive"))
      (node (ref "R45") (pin "1") (pinfunction "1_1") (pintype "passive"))
      (node (ref "R46") (pin "2") (pinfunction "2_2") (pintype "passive"))
    )
    (net (code "27") (name "Net-(D8-ANODE)") (class "Default")
      (node (ref "D8") (pin "2") (pinfunction "ANODE_2") (pintype "passive"))
      (node (ref "Q5") (pin "4") (pinfunction "G_4") (pintype "passive"))
      (node (ref "U5") (pin "3") (pinfunction "E_3") (pintype "passive"))
    )
    (net (code "28") (name "Net-(D8-CATHODE)") (class "Default")
      (node (ref "C22") (pin "2") (pinfunction "2_2") (pintype "passive"))
      (node (ref "D8") (pin "1") (pinfunction "CATHODE_1") (pintype "passive"))
      (node (ref "L3") (pin "2") (pinfunction "2_2") (pintype "passive"))
      (node (ref "Q6") (pin "5") (pinfunction "D_5") (pintype "passive"))
      (node (ref "R39") (pin "2") (pinfunction "2_2") (pintype "passive"))
      (node (ref "T1") (pin "7") (pinfunction "10_7") (pintype "passive"))
      (node (ref "T1") (pin "8") (pinfunction "11_8") (pintype "passive"))
      (node (ref "T1") (pin "9") (pinfunction "12_9") (pintype "passive"))
      (node (ref "U5") (pin "2") (pinfunction "C_2") (pintype "passive"))
    )
    (net (code "29") (name "Net-(D9-ANODE)") (class "Default")
      (node (ref "D9") (pin "2") (pinfunction "ANODE_2") (pintype "passive"))
      (node (ref "Q6") (pin "4") (pinfunction "G_4") (pintype "passive"))
      (node (ref "U11") (pin "3") (pinfunction "E_3") (pintype "passive"))
    )
    (net (code "30") (name "Net-(D9-CATHODE)") (class "Default")
      (node (ref "D9") (pin "1") (pinfunction "CATHODE_1") (pintype "passive"))
      (node (ref "Q5") (pin "5") (pinfunction "D_5") (pintype "passive"))
      (node (ref "R40") (pin "2") (pinfunction "2_2") (pintype "passive"))
      (node (ref "T1") (pin "10") (pinfunction "7_10") (pintype "passive"))
      (node (ref "T1") (pin "11") (pinfunction "8_11") (pintype "passive"))
      (node (ref "T1") (pin "12") (pinfunction "9_12") (pintype "passive"))
      (node (ref "U11") (pin "2") (pinfunction "C_2") (pintype "passive"))
    )
    (net (code "31") (name "Net-(D10-ANODE)") (class "Default")
      (node (ref "D10") (pin "2") (pinfunction "ANODE_2") (pintype "passive"))
      (node (ref "T1") (pin "5") (pinfunction "3_5") (pintype "passive"))
    )
    (net (code "32") (name "Net-(D10-CATHODE)") (class "Default")
      (node (ref "D10") (pin "1") (pinfunction "CATHODE_1") (pintype "passive"))
      (node (ref "D11") (pin "1") (pinfunction "CATHODE_1") (pintype "passive"))
      (node (ref "L5") (pin "2") (pinfunction "2_2") (pintype "bidirectional"))
    )
    (net (code "33") (name "Net-(D12-ANODE)") (class "Default")
      (node (ref "C32") (pin "2") (pinfunction "2_2") (pintype "passive"))
      (node (ref "D12") (pin "2") (pinfunction "ANODE_2") (pintype "passive"))
      (node (ref "R21") (pin "2") (pinfunction "2_2") (pintype "passive"))
      (node (ref "U9") (pin "1") (pinfunction "G_1") (pintype "passive"))
    )
    (net (code "34") (name "Net-(D13-ANODE)") (class "Default")
      (node (ref "D13") (pin "2") (pinfunction "ANODE_2") (pintype "passive"))
      (node (ref "R22") (pin "2") (pinfunction "2_2") (pintype "passive"))
      (node (ref "U7") (pin "1") (pinfunction "1_1") (pintype "passive"))
    )
    (net (code "35") (name "Net-(D13-CATHODE)") (class "Default")
      (node (ref "D13") (pin "1") (pinfunction "CATHODE_1") (pintype "passive"))
      (node (ref "U7") (pin "2") (pinfunction "2_2") (pintype "passive"))
      (node (ref "U8") (pin "4") (pinfunction "4_4") (pintype "passive"))
    )
    (net (code "36") (name "Net-(J1-Pad1)") (class "Default")
      (node (ref "J1") (pin "1") (pinfunction "1_1") (pintype "passive"))
      (node (ref "U1") (pin "23") (pinfunction "23_23") (pintype "passive"))
    )
    (net (code "37") (name "Net-(J1-Pad2)") (class "Default")
      (node (ref "J1") (pin "2") (pinfunction "2_2") (pintype "passive"))
      (node (ref "U1") (pin "22") (pinfunction "22_22") (pintype "passive"))
    )
    (net (code "38") (name "Net-(J1-Pad3)") (class "Default")
      (node (ref "J1") (pin "3") (pinfunction "3_3") (pintype "passive"))
      (node (ref "U1") (pin "20") (pinfunction "20_20") (pintype "passive"))
    )
    (net (code "39") (name "Net-(J1-Pad4)") (class "Default")
      (node (ref "J1") (pin "4") (pinfunction "4_4") (pintype "passive"))
      (node (ref "U1") (pin "17") (pinfunction "17_17") (pintype "passive"))
    )
    (net (code "40") (name "Net-(J1-Pad5)") (class "Default")
      (node (ref "J1") (pin "5") (pinfunction "5_5") (pintype "passive"))
      (node (ref "U1") (pin "16") (pinfunction "16_16") (pintype "passive"))
    )
    (net (code "41") (name "Net-(J1-Pad6)") (class "Default")
      (node (ref "J1") (pin "6") (pinfunction "6_6") (pintype "passive"))
      (node (ref "U1") (pin "19") (pinfunction "19_19") (pintype "passive"))
    )
    (net (code "42") (name "Net-(J1-Pad7)") (class "Default")
      (node (ref "J1") (pin "7") (pinfunction "7_7") (pintype "passive"))
      (node (ref "U1") (pin "14") (pinfunction "14_14") (pintype "passive"))
    )
    (net (code "43") (name "Net-(J1-Pad8)") (class "Default")
      (node (ref "J1") (pin "8") (pinfunction "8_8") (pintype "passive"))
      (node (ref "U1") (pin "13") (pinfunction "13_13") (pintype "passive"))
    )
    (net (code "44") (name "Net-(J2-Pad02)") (class "Default")
      (node (ref "J2") (pin "02") (pinfunction "02_02") (pintype "passive"))
      (node (ref "R31") (pin "2") (pinfunction "2_2") (pintype "passive"))
    )
    (net (code "45") (name "Net-(JP1-Pad1)") (class "Default")
      (node (ref "JP1") (pin "1") (pinfunction "1_1") (pintype "passive"))
      (node (ref "R62") (pin "2") (pinfunction "2_2") (pintype "passive"))
    )
    (net (code "46") (name "Net-(LED1-Pad2)") (class "Default")
      (node (ref "LED1") (pin "2") (pinfunction "2_2") (pintype "passive"))
      (node (ref "R61") (pin "1") (pinfunction "1_1") (pintype "passive"))
    )
    (net (code "47") (name "Net-(LED2-Pad2)") (class "Default")
      (node (ref "LED2") (pin "2") (pinfunction "2_2") (pintype "passive"))
      (node (ref "R60") (pin "1") (pinfunction "1_1") (pintype "passive"))
    )
    (net (code "48") (name "Net-(LED3-Pad2)") (class "Default")
      (node (ref "LED3") (pin "2") (pinfunction "2_2") (pintype "passive"))
      (node (ref "R59") (pin "1") (pinfunction "1_1") (pintype "passive"))
    )
    (net (code "49") (name "Net-(LED4-Pad2)") (class "Default")
      (node (ref "LED4") (pin "2") (pinfunction "2_2") (pintype "passive"))
      (node (ref "R56") (pin "1") (pinfunction "1_1") (pintype "passive"))
    )
    (net (code "50") (name "Net-(LED5-Pad2)") (class "Default")
      (node (ref "LED5") (pin "2") (pinfunction "2_2") (pintype "passive"))
      (node (ref "R57") (pin "1") (pinfunction "1_1") (pintype "passive"))
    )
    (net (code "51") (name "Net-(Q1-G)") (class "Default")
      (node (ref "C13") (pin "2") (pinfunction "2_2") (pintype "passive"))
      (node (ref "Q1") (pin "1") (pinfunction "G_1") (pintype "bidirectional"))
      (node (ref "R13") (pin "2") (pinfunction "2_2") (pintype "passive"))
      (node (ref "R9") (pin "1") (pinfunction "1_1") (pintype "passive"))
    )
    (net (code "52") (name "Net-(Q1-S)") (class "Default")
      (node (ref "C11") (pin "1") (pinfunction "1_1") (pintype "passive"))
      (node (ref "C13") (pin "1") (pinfunction "1_1") (pintype "passive"))
      (node (ref "C14") (pin "1") (pinfunction "1_1") (pintype "passive"))
      (node (ref "C15") (pin "1") (pinfunction "1_1") (pintype "passive"))
      (node (ref "C16") (pin "1") (pinfunction "1_1") (pintype "passive"))
      (node (ref "L2") (pin "2") (pinfunction "2_2") (pintype "passive"))
      (node (ref "Q1") (pin "2") (pinfunction "S_2") (pintype "bidirectional"))
      (node (ref "Q2") (pin "2") (pinfunction "S_2") (pintype "bidirectional"))
      (node (ref "Q3") (pin "2") (pinfunction "S_2") (pintype "bidirectional"))
      (node (ref "Q4") (pin "2") (pinfunction "S_2") (pintype "bidirectional"))
      (node (ref "R13") (pin "1") (pinfunction "1_1") (pintype "passive"))
      (node (ref "R14") (pin "1") (pinfunction "1_1") (pintype "passive"))
      (node (ref "R15") (pin "1") (pinfunction "1_1") (pintype "passive"))
      (node (ref "R16") (pin "1") (pinfunction "1_1") (pintype "passive"))
    )
    (net (code "53") (name "Net-(Q2-G)") (class "Default")
      (node (ref "C14") (pin "2") (pinfunction "2_2") (pintype "passive"))
      (node (ref "Q2") (pin "1") (pinfunction "G_1") (pintype "bidirectional"))
      (node (ref "R10") (pin "1") (pinfunction "1_1") (pintype "passive"))
      (node (ref "R14") (pin "2") (pinfunction "2_2") (pintype "passive"))
    )
    (net (code "54") (name "Net-(Q3-G)") (class "Default")
      (node (ref "C15") (pin "2") (pinfunction "2_2") (pintype "passive"))
      (node (ref "Q3") (pin "1") (pinfunction "G_1") (pintype "bidirectional"))
      (node (ref "R11") (pin "1") (pinfunction "1_1") (pintype "passive"))
      (node (ref "R15") (pin "2") (pinfunction "2_2") (pintype "passive"))
    )
    (net (code "55") (name "Net-(Q4-G)") (class "Default")
      (node (ref "C16") (pin "2") (pinfunction "2_2") (pintype "passive"))
      (node (ref "Q4") (pin "1") (pinfunction "G_1") (pintype "bidirectional"))
      (node (ref "R12") (pin "1") (pinfunction "1_1") (pintype "passive"))
      (node (ref "R16") (pin "2") (pinfunction "2_2") (pintype "passive"))
    )
    (net (code "56") (name "Net-(R1-Pad1)") (class "Default")
      (node (ref "R1") (pin "1") (pinfunction "1_1") (pintype "passive"))
      (node (ref "U1") (pin "8") (pinfunction "8_8") (pintype "passive"))
    )
    (net (code "57") (name "Net-(R2-Pad1)") (class "Default")
      (node (ref "R2") (pin "1") (pinfunction "1_1") (pintype "passive"))
      (node (ref "U1") (pin "9") (pinfunction "9_9") (pintype "passive"))
    )
    (net (code "58") (name "Net-(R3-Pad1)") (class "Default")
      (node (ref "R3") (pin "1") (pinfunction "1_1") (pintype "passive"))
      (node (ref "U1") (pin "11") (pinfunction "11_11") (pintype "passive"))
    )
    (net (code "59") (name "Net-(R4-Pad1)") (class "Default")
      (node (ref "R4") (pin "1") (pinfunction "1_1") (pintype "passive"))
      (node (ref "U1") (pin "12") (pinfunction "12_12") (pintype "passive"))
    )
    (net (code "60") (name "Net-(R30-Pad1)") (class "Default")
      (node (ref "R30") (pin "1") (pinfunction "1_1") (pintype "passive"))
      (node (ref "R31") (pin "3") (pinfunction "3_3") (pintype "passive"))
    )
    (net (code "61") (name "Net-(R37-Pad2)") (class "Default")
      (node (ref "R37") (pin "2") (pinfunction "2_2") (pintype "passive"))
      (node (ref "R38") (pin "2") (pinfunction "2_2") (pintype "passive"))
      (node (ref "U8") (pin "1") (pinfunction "1_1") (pintype "passive"))
      (node (ref "U8") (pin "2") (pinfunction "2_2") (pintype "passive"))
      (node (ref "U8") (pin "3") (pinfunction "3_3") (pintype "passive"))
    )
    (net (code "62") (name "Net-(R68-Pad1)") (class "Default")
      (node (ref "R68") (pin "1") (pinfunction "1_1") (pintype "passive"))
      (node (ref "U1") (pin "4") (pinfunction "4_4") (pintype "passive"))
    )
    (net (code "63") (name "Net-(T1-5)") (class "Default")
      (node (ref "C41") (pin "2") (pinfunction "2_2") (pintype "passive"))
      (node (ref "T1") (pin "3") (pinfunction "6_3") (pintype "passive"))
      (node (ref "T1") (pin "4") (pinfunction "5_4") (pintype "passive"))
      (node (ref "U8") (pin "5") (pinfunction "5_5") (pintype "passive"))
      (node (ref "U8") (pin "6") (pinfunction "6_6") (pintype "passive"))
      (node (ref "U8") (pin "7") (pinfunction "7_7") (pintype "passive"))
      (node (ref "U8") (pin "8") (pinfunction "8_8") (pintype "passive"))
    )
    (net (code "64") (name "Net-(U2-AMPS_CTL)") (class "Default")
      (node (ref "R30") (pin "2") (pinfunction "2_2") (pintype "passive"))
      (node (ref "U2") (pin "8") (pinfunction "AMPS_CTL_8") (pintype "input"))
    )
    (net (code "65") (name "Net-(U2-CLS1)") (class "Default")
      (node (ref "R24") (pin "2") (pinfunction "2_2") (pintype "passive"))
      (node (ref "U2") (pin "3") (pinfunction "CLS1_3") (pintype "bidirectional"))
    )
    (net (code "66") (name "Net-(U2-CLS2)") (class "Default")
      (node (ref "R27") (pin "2") (pinfunction "2_2") (pintype "passive"))
      (node (ref "U2") (pin "6") (pinfunction "CLS2_6") (pintype "bidirectional"))
    )
    (net (code "67") (name "Net-(U2-DEN)") (class "Default")
      (node (ref "R23") (pin "2") (pinfunction "2_2") (pintype "passive"))
      (node (ref "U2") (pin "2") (pinfunction "DEN_2") (pintype "bidirectional"))
    )
    (net (code "68") (name "Net-(U2-REF)") (class "Default")
      (node (ref "R32") (pin "2") (pinfunction "2_2") (pintype "passive"))
      (node (ref "TP6") (pin "TP") (pinfunction "TP_TP") (pintype "passive"))
      (node (ref "U2") (pin "7") (pinfunction "REF_7") (pintype "input"))
    )
    (net (code "69") (name "Net-(U2-UVLO_SEL)") (class "Default")
      (node (ref "TP1") (pin "TP") (pinfunction "TP_TP") (pintype "passive"))
      (node (ref "U2") (pin "16") (pinfunction "UVLO_SEL_16") (pintype "input"))
    )
    (net (code "70") (name "Net-(U3-AUX)") (class "Default")
      (node (ref "C32") (pin "1") (pinfunction "1_1") (pintype "passive"))
      (node (ref "U3") (pin "14") (pinfunction "AUX_14") (pintype "output"))
    )
    (net (code "71") (name "Net-(U3-CS)") (class "Default")
      (node (ref "C24") (pin "2") (pinfunction "2_2") (pintype "passive"))
      (node (ref "R33") (pin "2") (pinfunction "2_2") (pintype "passive"))
      (node (ref "R37") (pin "1") (pinfunction "1_1") (pintype "passive"))
      (node (ref "U3") (pin "9") (pinfunction "CS_9") (pintype "input"))
    )
    (net (code "72") (name "Net-(U3-FB)") (class "Default")
      (node (ref "C31") (pin "1") (pinfunction "1_1") (pintype "passive"))
      (node (ref "R36") (pin "1") (pinfunction "1_1") (pintype "passive"))
      (node (ref "U3") (pin "11") (pinfunction "FB_11") (pintype "input"))
      (node (ref "U6") (pin "4") (pinfunction "CT_4") (pintype "passive"))
    )
    (net (code "73") (name "Net-(U3-LINEOV)") (class "Default")
      (node (ref "R17") (pin "2") (pinfunction "2_2") (pintype "passive"))
      (node (ref "R19") (pin "2") (pinfunction "2_2") (pintype "passive"))
      (node (ref "U3") (pin "19") (pinfunction "LINEOV_19") (pintype "input"))
    )
    (net (code "74") (name "Net-(U3-LINEUV)") (class "Default")
      (node (ref "R18") (pin "2") (pinfunction "2_2") (pintype "passive"))
      (node (ref "R20") (pin "2") (pinfunction "2_2") (pintype "passive"))
      (node (ref "U3") (pin "18") (pinfunction "LINEUV_18") (pintype "input"))
    )
    (net (code "75") (name "Net-(U3-OUT)") (class "Default")
      (node (ref "R22") (pin "1") (pinfunction "1_1") (pintype "passive"))
      (node (ref "U3") (pin "15") (pinfunction "OUT_15") (pintype "output"))
    )
    (net (code "76") (name "Net-(U3-PVDD)") (class "Default")
      (node (ref "C23") (pin "1") (pinfunction "1_1") (pintype "passive"))
      (node (ref "C25") (pin "2") (pinfunction "2_2") (pintype "passive"))
      (node (ref "L5") (pin "1") (pinfunction "1_1") (pintype "bidirectional"))
      (node (ref "U3") (pin "16") (pinfunction "PVDD_16") (pintype "power_in"))
      (node (ref "U3") (pin "17") (pinfunction "VDD_17") (pintype "power_in"))
    )
    (net (code "77") (name "Net-(U3-ROFF)") (class "Default")
      (node (ref "R29") (pin "1") (pinfunction "1_1") (pintype "passive"))
      (node (ref "U3") (pin "5") (pinfunction "ROFF_5") (pintype "input"))
    )
    (net (code "78") (name "Net-(U3-RON)") (class "Default")
      (node (ref "R28") (pin "1") (pinfunction "1_1") (pintype "passive"))
      (node (ref "U3") (pin "4") (pinfunction "RON_4") (pintype "input"))
    )
    (net (code "79") (name "Net-(U3-RSLOPE)") (class "Default")
      (node (ref "R34") (pin "2") (pinfunction "2_2") (pintype "passive"))
      (node (ref "U3") (pin "10") (pinfunction "RSLOPE_10") (pintype "input"))
    )
    (net (code "80") (name "Net-(U3-RTDEL)") (class "Default")
      (node (ref "R25") (pin "1") (pinfunction "1_1") (pintype "passive"))
      (node (ref "U3") (pin "3") (pinfunction "RTDEL_3") (pintype "input"))
    )
    (net (code "81") (name "Net-(U3-VREF)") (class "Default")
      (node (ref "C27") (pin "1") (pinfunction "1_1") (pintype "passive"))
      (node (ref "R33") (pin "1") (pinfunction "1_1") (pintype "passive"))
      (node (ref "R35") (pin "2") (pinfunction "2_2") (pintype "passive"))
      (node (ref "R36") (pin "2") (pinfunction "2_2") (pintype "passive"))
      (node (ref "U3") (pin "6") (pinfunction "VREF_6") (pintype "output"))
    )
    (net (code "82") (name "Net-(U4-CATHODE)") (class "Default")
      (node (ref "C22") (pin "1") (pinfunction "1_1") (pintype "passive"))
      (node (ref "R39") (pin "1") (pinfunction "1_1") (pintype "passive"))
      (node (ref "U4") (pin "1") (pinfunction "CATHODE_1") (pintype "passive"))
      (node (ref "U5") (pin "1") (pinfunction "B_1") (pintype "passive"))
    )
    (net (code "83") (name "Net-(U6-A)") (class "Default")
      (node (ref "R41") (pin "1") (pinfunction "1_1") (pintype "passive"))
      (node (ref "U6") (pin "1") (pinfunction "A_1") (pintype "passive"))
    )
    (net (code "84") (name "Net-(U9-D)") (class "Default")
      (node (ref "C41") (pin "1") (pinfunction "1_1") (pintype "passive"))
      (node (ref "U9") (pin "2") (pinfunction "D_2") (pintype "passive"))
    )
    (net (code "85") (name "Net-(U10-CATHODE)") (class "Default")
      (node (ref "R40") (pin "1") (pinfunction "1_1") (pintype "passive"))
      (node (ref "U10") (pin "1") (pinfunction "CATHODE_1") (pintype "passive"))
      (node (ref "U11") (pin "1") (pinfunction "B_1") (pintype "passive"))
    )
    (net (code "86") (name "Net-(U12-REF)") (class "Default")
      (node (ref "C26") (pin "2") (pinfunction "2_2") (pintype "passive"))
      (node (ref "C28") (pin "2") (pinfunction "2_2") (pintype "passive"))
      (node (ref "R46") (pin "1") (pinfunction "1_1") (pintype "passive"))
      (node (ref "R47") (pin "2") (pinfunction "2_2") (pintype "passive"))
      (node (ref "U12") (pin "4") (pinfunction "REF_4") (pintype "input"))
    )
    (net (code "87") (name "Net-(U13-ILIM)") (class "Default")
      (node (ref "R52") (pin "2") (pinfunction "2_2") (pintype "passive"))
      (node (ref "U13") (pin "3") (pinfunction "ILIM_3") (pintype "input"))
    )
    (net (code "88") (name "Net-(U13-RT)") (class "Default")
      (node (ref "R51") (pin "2") (pinfunction "2_2") (pintype "passive"))
      (node (ref "U13") (pin "5") (pinfunction "RT_5") (pintype "input"))
    )
    (net (code "89") (name "Net-(U13-SS)") (class "Default")
      (node (ref "C44") (pin "2") (pinfunction "2_2") (pintype "passive"))
      (node (ref "U13") (pin "4") (pinfunction "SS_4") (pintype "input"))
    )
    (net (code "90") (name "Net-(U13-SW)") (class "Default")
      (node (ref "L6") (pin "2") (pinfunction "2_2") (pintype "passive"))
      (node (ref "R49") (pin "1") (pinfunction "1_1") (pintype "passive"))
      (node (ref "U13") (pin "1") (pinfunction "SW_1") (pintype "power_in"))
    )
    (net (code "91") (name "Net-(U13-VOUT_FB)") (class "Default")
      (node (ref "C43") (pin "1") (pinfunction "1_1") (pintype "passive"))
      (node (ref "R50") (pin "1") (pinfunction "1_1") (pintype "passive"))
      (node (ref "R53") (pin "2") (pinfunction "2_2") (pintype "passive"))
      (node (ref "U13") (pin "8") (pinfunction "VOUT_FB_8") (pintype "passive"))
    )
    (net (code "92") (name "Net-(U14-RBIAS)") (class "Default")
      (node (ref "R55") (pin "2") (pinfunction "2_2") (pintype "passive"))
      (node (ref "U14") (pin "14") (pinfunction "RBIAS_14") (pintype "input"))
    )
    (net (code "93") (name "Net-(U14-VCAP)") (class "Default")
      (node (ref "C54") (pin "2") (pinfunction "2_2") (pintype "passive"))
      (node (ref "U14") (pin "1") (pinfunction "VCAP_1") (pintype "input"))
    )
    (net (code "94") (name "OSC1") (class "Default")
      (node (ref "C53") (pin "2") (pinfunction "2_2") (pintype "passive"))
      (node (ref "U14") (pin "23") (pinfunction "OSC1_23") (pintype "input"))
      (node (ref "Y1") (pin "1") (pinfunction "1_1") (pintype "passive"))
    )
    (net (code "95") (name "OSC2") (class "Default")
      (node (ref "C52") (pin "2") (pinfunction "2_2") (pintype "passive"))
      (node (ref "U14") (pin "24") (pinfunction "OSC2_24") (pintype "output"))
      (node (ref "Y1") (pin "3") (pinfunction "2_3") (pintype "passive"))
    )
    (net (code "96") (name "PG") (class "Default")
      (node (ref "R26") (pin "1") (pinfunction "1_1") (pintype "passive"))
      (node (ref "R48") (pin "1") (pinfunction "1_1") (pintype "passive"))
      (node (ref "U13") (pin "7") (pinfunction "EN_7") (pintype "input"))
      (node (ref "U2") (pin "13") (pinfunction "PG_13") (pintype "output"))
    )
    (net (code "97") (name "PR12") (class "Default")
      (node (ref "C6") (pin "2") (pinfunction "2_2") (pintype "passive"))
      (node (ref "D1") (pin "2") (pinfunction "2_2") (pintype "passive"))
      (node (ref "Q1") (pin "3") (pinfunction "D_3") (pintype "bidirectional"))
      (node (ref "R10") (pin "2") (pinfunction "2_2") (pintype "passive"))
      (node (ref "U1") (pin "24") (pinfunction "24_24") (pintype "passive"))
    )
    (net (code "98") (name "PR36") (class "Default")
      (node (ref "C7") (pin "2") (pinfunction "2_2") (pintype "passive"))
      (node (ref "D2") (pin "2") (pinfunction "2_2") (pintype "passive"))
      (node (ref "Q2") (pin "3") (pinfunction "D_3") (pintype "bidirectional"))
      (node (ref "R9") (pin "2") (pinfunction "2_2") (pintype "passive"))
      (node (ref "U1") (pin "21") (pinfunction "21_21") (pintype "passive"))
    )
    (net (code "99") (name "PR45") (class "Default")
      (node (ref "C8") (pin "2") (pinfunction "2_2") (pintype "passive"))
      (node (ref "D3") (pin "2") (pinfunction "2_2") (pintype "passive"))
      (node (ref "Q3") (pin "3") (pinfunction "D_3") (pintype "bidirectional"))
      (node (ref "R12") (pin "2") (pinfunction "2_2") (pintype "passive"))
      (node (ref "U1") (pin "18") (pinfunction "18_18") (pintype "passive"))
    )
    (net (code "100") (name "PR78") (class "Default")
      (node (ref "C9") (pin "2") (pinfunction "2_2") (pintype "passive"))
      (node (ref "D4") (pin "2") (pinfunction "2_2") (pintype "passive"))
      (node (ref "Q4") (pin "3") (pinfunction "D_3") (pintype "bidirectional"))
      (node (ref "R11") (pin "2") (pinfunction "2_2") (pintype "passive"))
      (node (ref "U1") (pin "15") (pinfunction "15_15") (pintype "passive"))
    )
    (net (code "101") (name "RESET_ETH") (class "Default")
      (node (ref "J4") (pin "2") (pinfunction "2_2") (pintype "passive"))
      (node (ref "R58") (pin "2") (pinfunction "2_2") (pintype "passive"))
      (node (ref "U14") (pin "10") (pinfunction "~{RESET}_10") (pintype "input"))
    )
    (net (code "102") (name "RTN") (class "Default")
      (node (ref "C17") (pin "1") (pinfunction "1_1") (pintype "passive"))
      (node (ref "C18") (pin "1") (pinfunction "1_1") (pintype "passive"))
      (node (ref "C20") (pin "2") (pinfunction "2_2") (pintype "passive"))
      (node (ref "C23") (pin "2") (pinfunction "2_2") (pintype "passive"))
      (node (ref "C24") (pin "1") (pinfunction "1_1") (pintype "passive"))
      (node (ref "C25") (pin "1") (pinfunction "1_1") (pintype "passive"))
      (node (ref "C27") (pin "2") (pinfunction "2_2") (pintype "passive"))
      (node (ref "C30") (pin "1") (pinfunction "1_1") (pintype "passive"))
      (node (ref "C34") (pin "1") (pinfunction "1_1") (pintype "passive"))
      (node (ref "C35") (pin "1") (pinfunction "1_1") (pintype "passive"))
      (node (ref "C36") (pin "1") (pinfunction "1_1") (pintype "passive"))
      (node (ref "C37") (pin "1") (pinfunction "1_1") (pintype "passive"))
      (node (ref "C39") (pin "1") (pinfunction "1_1") (pintype "passive"))
      (node (ref "C55") (pin "1") (pinfunction "1_1") (pintype "passive"))
      (node (ref "C56") (pin "1") (pinfunction "1_1") (pintype "passive"))
      (node (ref "C57") (pin "1") (pinfunction "1_1") (pintype "passive"))
      (node (ref "D11") (pin "2") (pinfunction "ANODE_2") (pintype "passive"))
      (node (ref "D12") (pin "1") (pinfunction "CATHODE_1") (pintype "passive"))
      (node (ref "J9") (pin "2") (pinfunction "2_2") (pintype "passive"))
      (node (ref "R19") (pin "1") (pinfunction "1_1") (pintype "passive"))
      (node (ref "R20") (pin "1") (pinfunction "1_1") (pintype "passive"))
      (node (ref "R21") (pin "1") (pinfunction "1_1") (pintype "passive"))
      (node (ref "R25") (pin "2") (pinfunction "2_2") (pintype "passive"))
      (node (ref "R28") (pin "2") (pinfunction "2_2") (pintype "passive"))
      (node (ref "R29") (pin "2") (pinfunction "2_2") (pintype "passive"))
      (node (ref "R34") (pin "1") (pinfunction "1_1") (pintype "passive"))
      (node (ref "R38") (pin "1") (pinfunction "1_1") (pintype "passive"))
      (node (ref "T1") (pin "6") (pinfunction "4_6") (pintype "passive"))
      (node (ref "U2") (pin "11") (pinfunction "RTN_2_11") (pintype "output"))
      (node (ref "U2") (pin "12") (pinfunction "RTN_12") (pintype "output"))
      (node (ref "U3") (pin "13") (pinfunction "PGND_13") (pintype "power_in"))
      (node (ref "U3") (pin "8") (pinfunction "GND_8") (pintype "power_in"))
      (node (ref "U6") (pin "3") (pinfunction "ET_3") (pintype "passive"))
      (node (ref "U7") (pin "3") (pinfunction "3_3") (pintype "passive"))
      (node (ref "U9") (pin "3") (pinfunction "S_3") (pintype "passive"))
    )
    (net (code "103") (name "RXD_N") (class "Default")
      (node (ref "R67") (pin "1") (pinfunction "1_1") (pintype "passive"))
      (node (ref "U1") (pin "6") (pinfunction "6_6") (pintype "passive"))
      (node (ref "U14") (pin "12") (pinfunction "TPIN-_12") (pintype "input"))
    )
    (net (code "104") (name "RXD_P") (class "Default")
      (node (ref "R66") (pin "1") (pinfunction "1_1") (pintype "passive"))
      (node (ref "U1") (pin "5") (pinfunction "5_5") (pintype "passive"))
      (node (ref "U14") (pin "13") (pinfunction "TPIN+_13") (pintype "input"))
    )
    (net (code "105") (name "SPI_MISO") (class "Default")
      (node (ref "J10") (pin "1") (pinfunction "1_1") (pintype "passive"))
      (node (ref "U14") (pin "6") (pinfunction "SO_6") (pintype "output"))
    )
    (net (code "106") (name "SPI_MOSI") (class "Default")
      (node (ref "J10") (pin "2") (pinfunction "2_2") (pintype "passive"))
      (node (ref "U14") (pin "7") (pinfunction "SI_7") (pintype "input"))
    )
    (net (code "107") (name "SPI_SCLK") (class "Default")
      (node (ref "J10") (pin "3") (pinfunction "3_3") (pintype "passive"))
      (node (ref "U14") (pin "8") (pinfunction "SCK_8") (pintype "input"))
    )
    (net (code "108") (name "SS") (class "Default")
      (node (ref "C30") (pin "2") (pinfunction "2_2") (pintype "passive"))
      (node (ref "R26") (pin "2") (pinfunction "2_2") (pintype "passive"))
      (node (ref "U3") (pin "12") (pinfunction "SS_SD_12") (pintype "input"))
    )
    (net (code "109") (name "TPH") (class "Default")
      (node (ref "LED1") (pin "1") (pinfunction "1_1") (pintype "passive"))
      (node (ref "U2") (pin "18") (pinfunction "TPH_18") (pintype "output"))
    )
    (net (code "110") (name "TPL") (class "Default")
      (node (ref "LED2") (pin "1") (pinfunction "1_1") (pintype "passive"))
      (node (ref "U2") (pin "17") (pinfunction "TPL_17") (pintype "output"))
    )
    (net (code "111") (name "TXD_N") (class "Default")
      (node (ref "R65") (pin "1") (pinfunction "1_1") (pintype "passive"))
      (node (ref "U1") (pin "3") (pinfunction "3_3") (pintype "passive"))
      (node (ref "U14") (pin "16") (pinfunction "TPOUT-_16") (pintype "output"))
    )
    (net (code "112") (name "TXD_P") (class "Default")
      (node (ref "R64") (pin "1") (pinfunction "1_1") (pintype "passive"))
      (node (ref "U1") (pin "2") (pinfunction "2_2") (pintype "passive"))
      (node (ref "U14") (pin "17") (pinfunction "TPOUT+_17") (pintype "output"))
    )
    (net (code "113") (name "VCOUT") (class "Default")
      (node (ref "R59") (pin "2") (pinfunction "2_2") (pintype "passive"))
      (node (ref "R60") (pin "2") (pinfunction "2_2") (pintype "passive"))
      (node (ref "R61") (pin "2") (pinfunction "2_2") (pintype "passive"))
    )
    (net (code "114") (name "VC_IN") (class "Default")
      (node (ref "C17") (pin "2") (pinfunction "2_2") (pintype "passive"))
      (node (ref "U2") (pin "15") (pinfunction "VC_IN_15") (pintype "power_in"))
    )
    (net (code "115") (name "VC_OUT") (class "Default")
      (node (ref "C18") (pin "2") (pinfunction "2_2") (pintype "passive"))
      (node (ref "U2") (pin "14") (pinfunction "VC_OUT_14") (pintype "power_in"))
    )
    (net (code "116") (name "VDD") (class "Default")
      (node (ref "C12") (pin "2") (pinfunction "2_2") (pintype "passive"))
      (node (ref "C19") (pin "2") (pinfunction "2_2") (pintype "passive"))
      (node (ref "C20") (pin "1") (pinfunction "1_1") (pintype "passive"))
      (node (ref "C34") (pin "2") (pinfunction "2_2") (pintype "passive"))
      (node (ref "D5") (pin "1") (pinfunction "1_1") (pintype "passive"))
      (node (ref "J9") (pin "1") (pinfunction "1_1") (pintype "passive"))
      (node (ref "L1") (pin "1") (pinfunction "1_1") (pintype "passive"))
      (node (ref "L4") (pin "2") (pinfunction "2_2") (pintype "passive"))
      (node (ref "R17") (pin "1") (pinfunction "1_1") (pintype "passive"))
      (node (ref "R18") (pin "1") (pinfunction "1_1") (pintype "passive"))
      (node (ref "R23") (pin "1") (pinfunction "1_1") (pintype "passive"))
      (node (ref "U2") (pin "1") (pinfunction "VDD_1") (pintype "power_in"))
      (node (ref "U3") (pin "1") (pinfunction "VIN_1") (pintype "power_in"))
    )
    (net (code "117") (name "VDD_P") (class "Default")
      (node (ref "C3") (pin "2") (pinfunction "2_2") (pintype "passive"))
      (node (ref "C35") (pin "2") (pinfunction "2_2") (pintype "passive"))
      (node (ref "C36") (pin "2") (pinfunction "2_2") (pintype "passive"))
      (node (ref "C37") (pin "2") (pinfunction "2_2") (pintype "passive"))
      (node (ref "C4") (pin "2") (pinfunction "2_2") (pintype "passive"))
      (node (ref "C40") (pin "2") (pinfunction "2_2") (pintype "passive"))
      (node (ref "C46") (pin "2") (pinfunction "2_2") (pintype "passive"))
      (node (ref "L4") (pin "1") (pinfunction "1_1") (pintype "passive"))
      (node (ref "R48") (pin "2") (pinfunction "2_2") (pintype "passive"))
      (node (ref "T1") (pin "1") (pinfunction "1_1") (pintype "passive"))
      (node (ref "T1") (pin "2") (pinfunction "2_2") (pintype "passive"))
      (node (ref "TP11") (pin "TP") (pinfunction "TP_TP") (pintype "passive"))
      (node (ref "U13") (pin "2") (pinfunction "VIN_2") (pintype "power_in"))
    )
    (net (code "118") (name "VSS") (class "Default")
      (node (ref "C19") (pin "1") (pinfunction "1_1") (pintype "passive"))
      (node (ref "J2") (pin "01") (pinfunction "01_01") (pintype "passive"))
      (node (ref "J3") (pin "01") (pinfunction "01_01") (pintype "passive"))
      (node (ref "JP1") (pin "3") (pinfunction "3_3") (pintype "passive"))
      (node (ref "R24") (pin "1") (pinfunction "1_1") (pintype "passive"))
      (node (ref "R27") (pin "1") (pinfunction "1_1") (pintype "passive"))
      (node (ref "R32") (pin "1") (pinfunction "1_1") (pintype "passive"))
      (node (ref "R62") (pin "1") (pinfunction "1_1") (pintype "passive"))
      (node (ref "U2") (pin "21") (pinfunction "PAD_21") (pintype "power_in"))
      (node (ref "U2") (pin "4") (pinfunction "VSS_2_4") (pintype "power_in"))
      (node (ref "U2") (pin "5") (pinfunction "VSS_5") (pintype "power_in"))
    )
    (net (code "119") (name "VSS1") (class "Default")
      (node (ref "C12") (pin "1") (pinfunction "1_1") (pintype "passive"))
      (node (ref "D5") (pin "2") (pinfunction "2_2") (pintype "passive"))
      (node (ref "J3") (pin "02") (pinfunction "02_02") (pintype "passive"))
      (node (ref "L2") (pin "1") (pinfunction "1_1") (pintype "passive"))
    )
    (net (code "120") (name "unconnected-(R31-Pad1)") (class "Default")
      (node (ref "R31") (pin "1") (pinfunction "1_1") (pintype "passive"))
    )
    (net (code "121") (name "unconnected-(U1-Pad7)") (class "Default")
      (node (ref "U1") (pin "7") (pinfunction "7_7") (pintype "passive"))
    )
    (net (code "122") (name "unconnected-(U1-Pad10)") (class "Default")
      (node (ref "U1") (pin "10") (pinfunction "10_10") (pintype "passive"))
    )
    (net (code "123") (name "unconnected-(U2-APD-Pad10)") (class "Default")
      (node (ref "U2") (pin "10") (pinfunction "APD_10") (pintype "input"))
    )
    (net (code "124") (name "unconnected-(U2-NC-Pad20)") (class "Default")
      (node (ref "U2") (pin "20") (pinfunction "NC_20") (pintype "passive"))
    )
    (net (code "125") (name "unconnected-(U3-NC-Pad20)") (class "Default")
      (node (ref "U3") (pin "20") (pinfunction "NC_20") (pintype "passive"))
    )
    (net (code "126") (name "unconnected-(U3-NC_2-Pad2)") (class "Default")
      (node (ref "U3") (pin "2") (pinfunction "NC_2_2") (pintype "passive"))
    )
    (net (code "127") (name "unconnected-(U3-SYNC-Pad7)") (class "Default")
      (node (ref "U3") (pin "7") (pinfunction "SYNC_7") (pintype "input"))
    )
    (net (code "128") (name "unconnected-(U13-PGOOD-Pad6)") (class "Default")
      (node (ref "U13") (pin "6") (pinfunction "PGOOD_6") (pintype "open_collector"))
    )
    (net (code "129") (name "unconnected-(U14-NC-Pad5)") (class "Default")
      (node (ref "U14") (pin "5") (pinfunction "NC_5") (pintype "bidirectional"))
    )
  )
)
